# eps.net
KiCad netlist of a schematic drawn in EAGLE
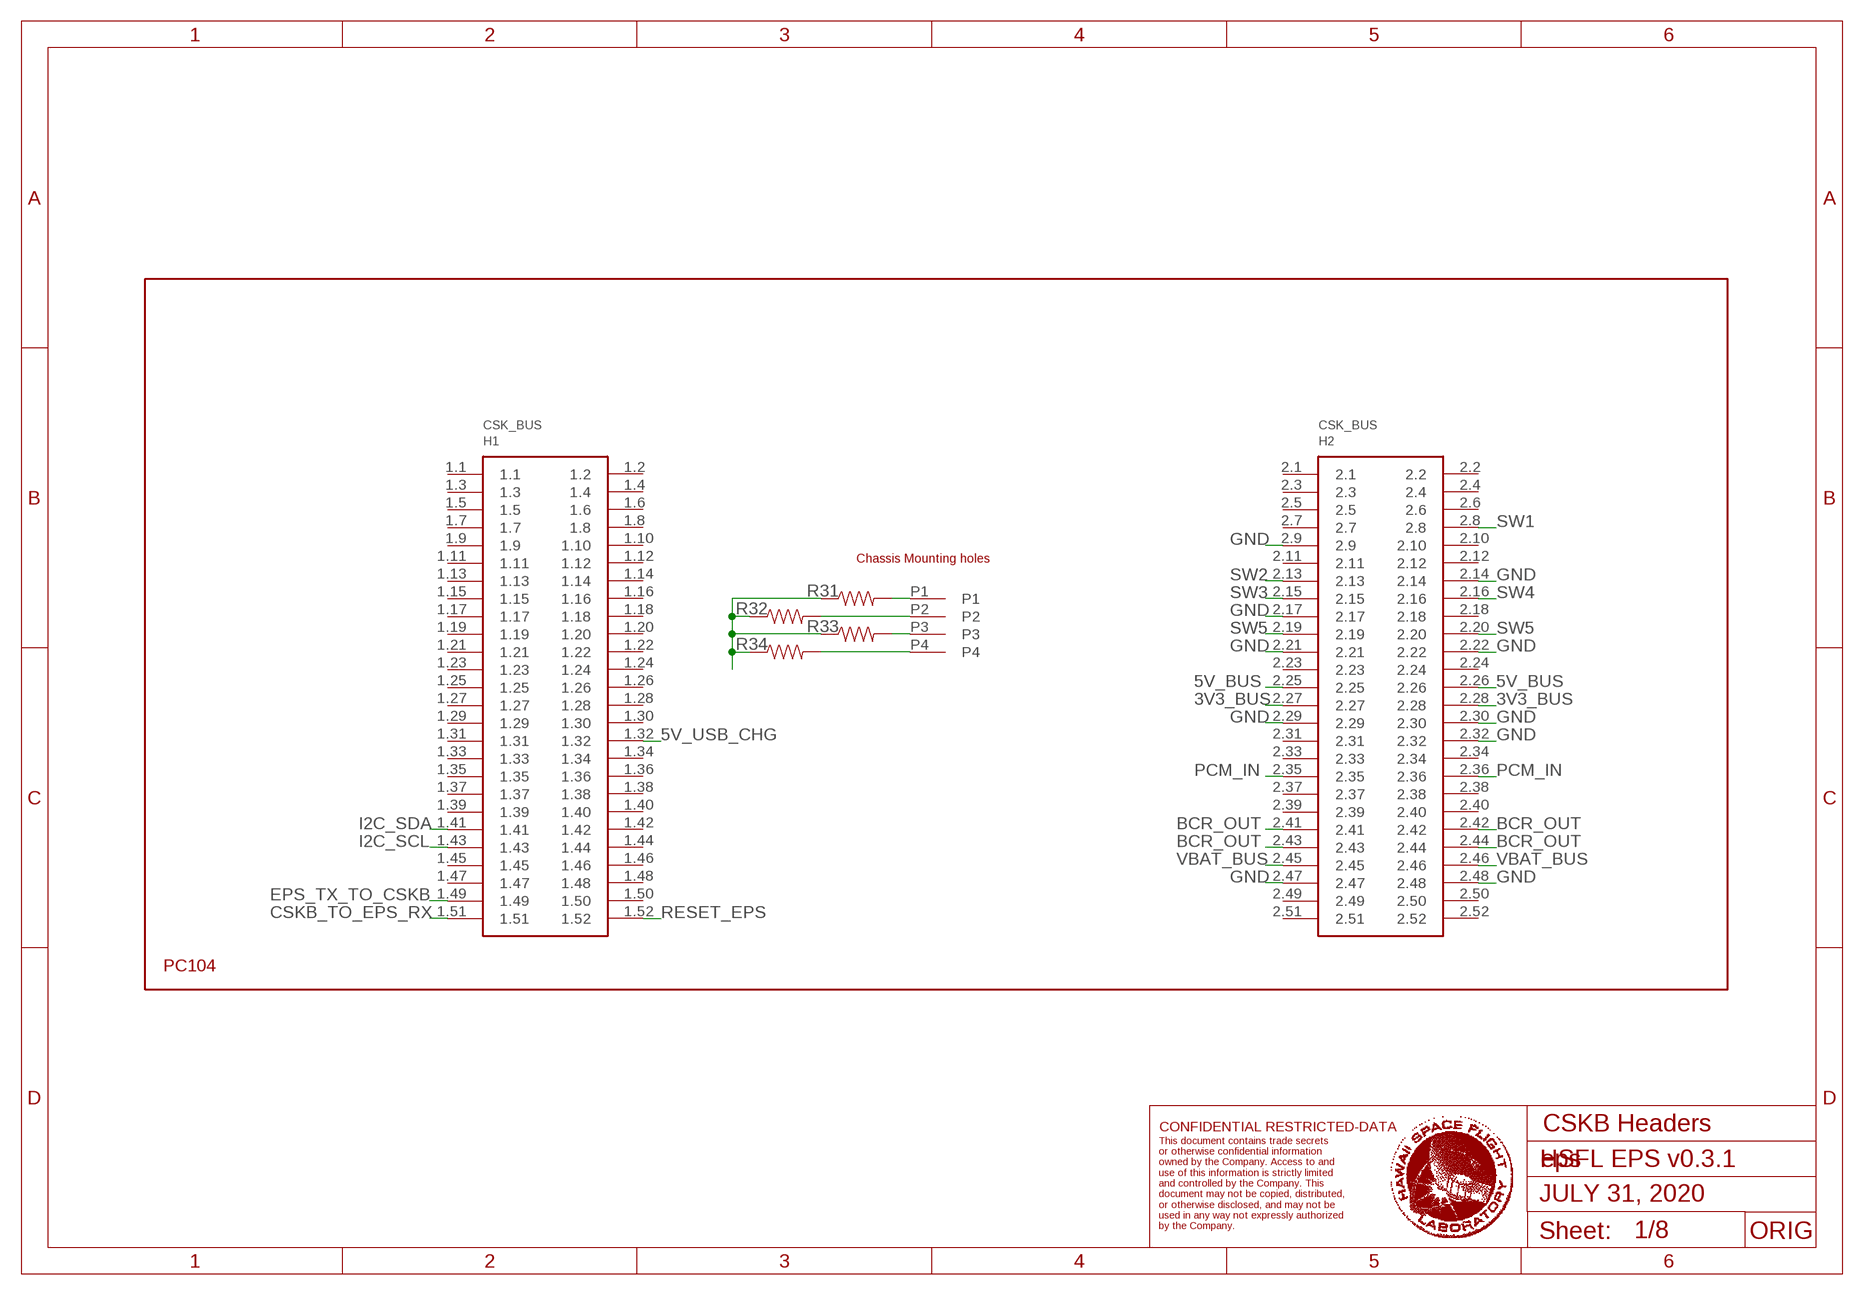
[diagram p0: schematic, sheet 1]
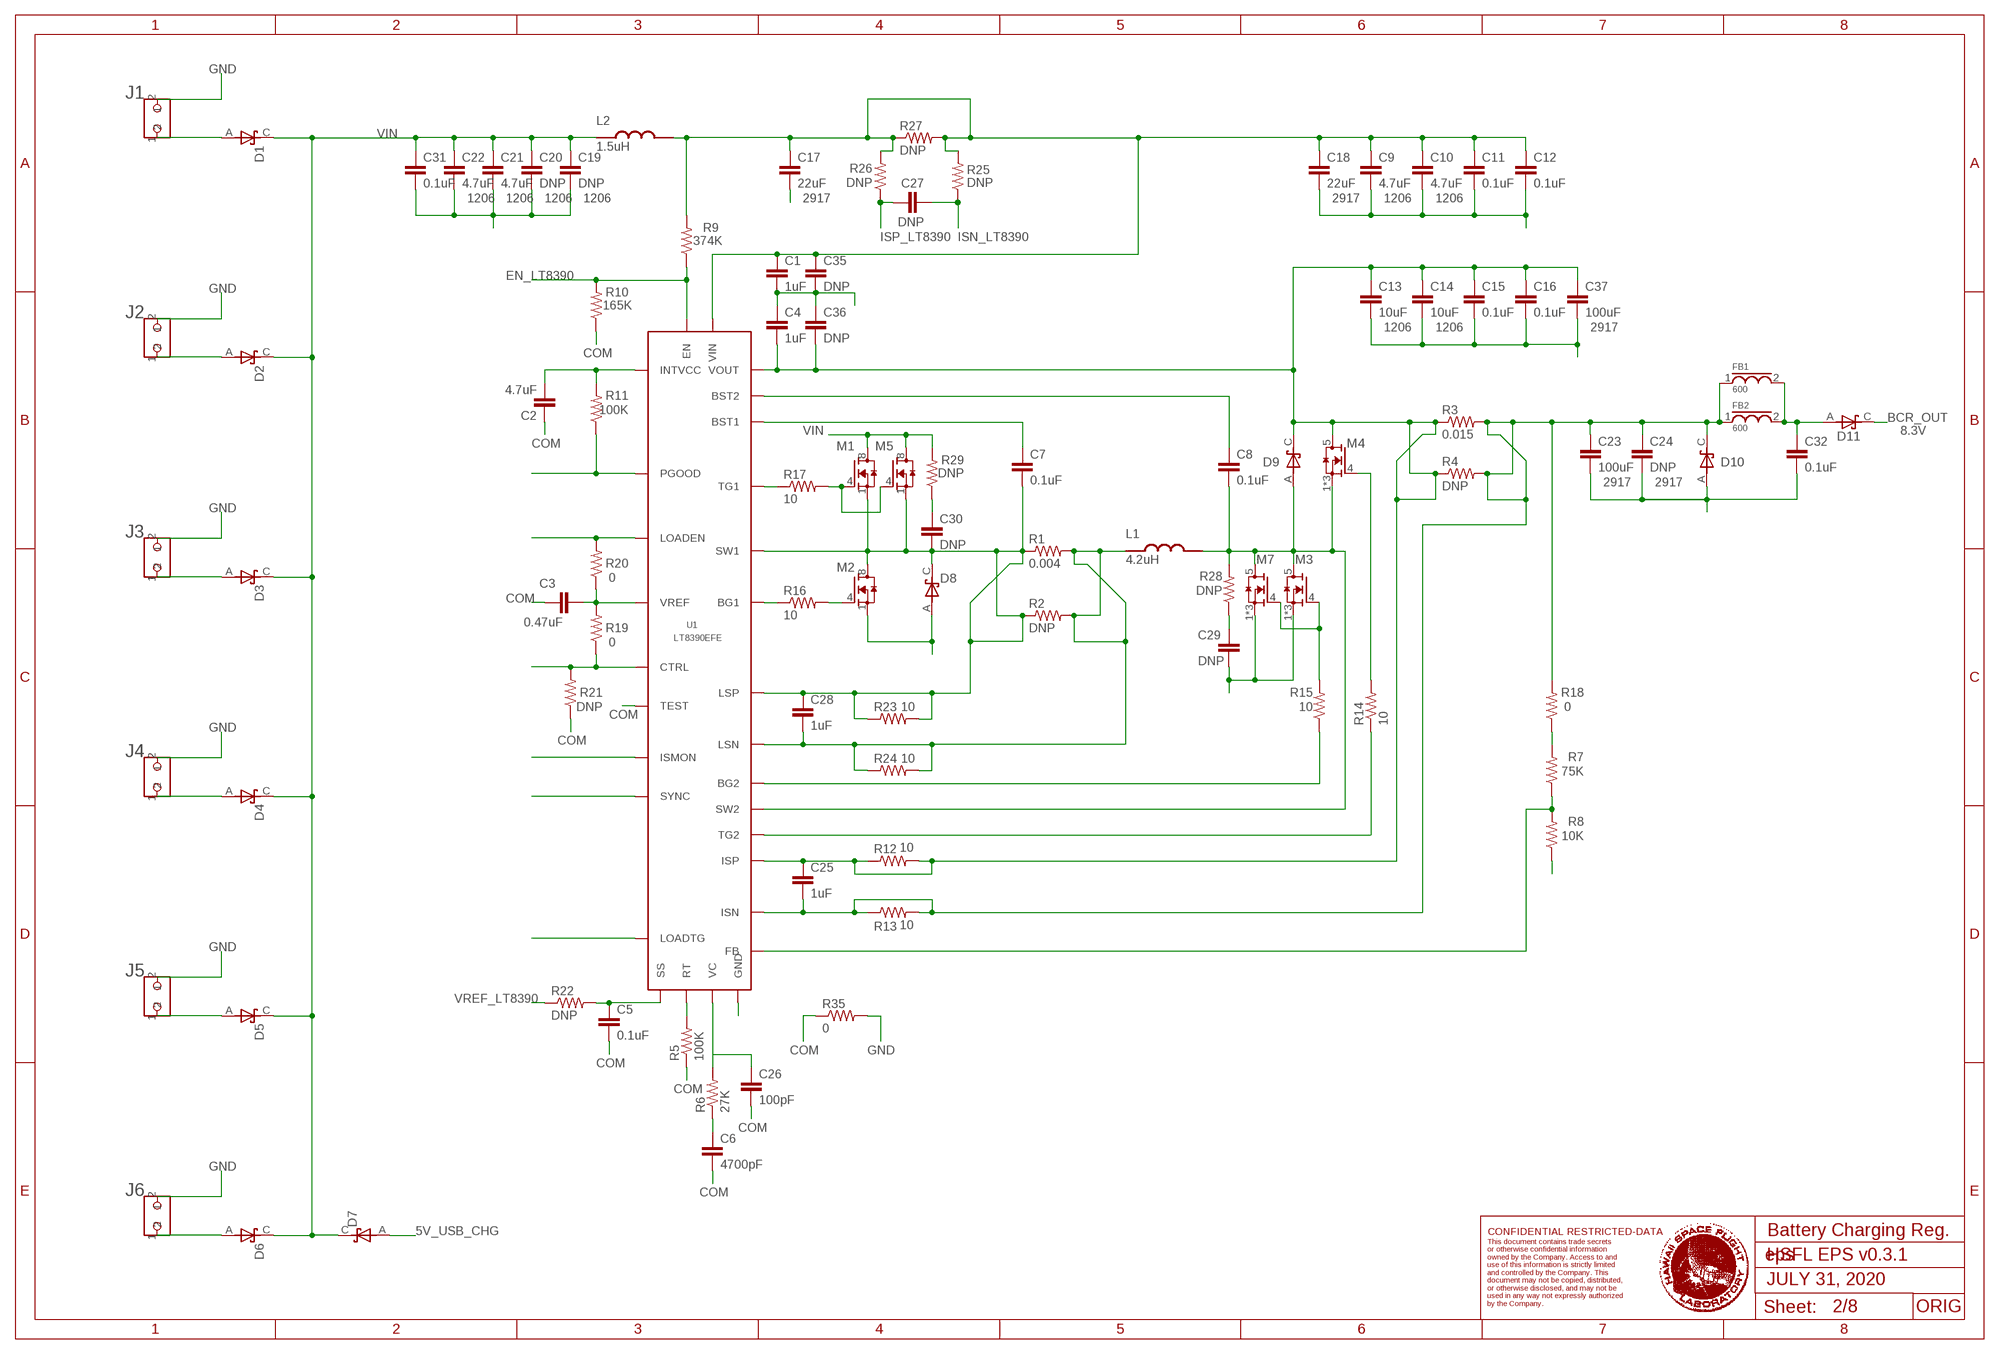
[diagram p1: schematic, sheet 2]
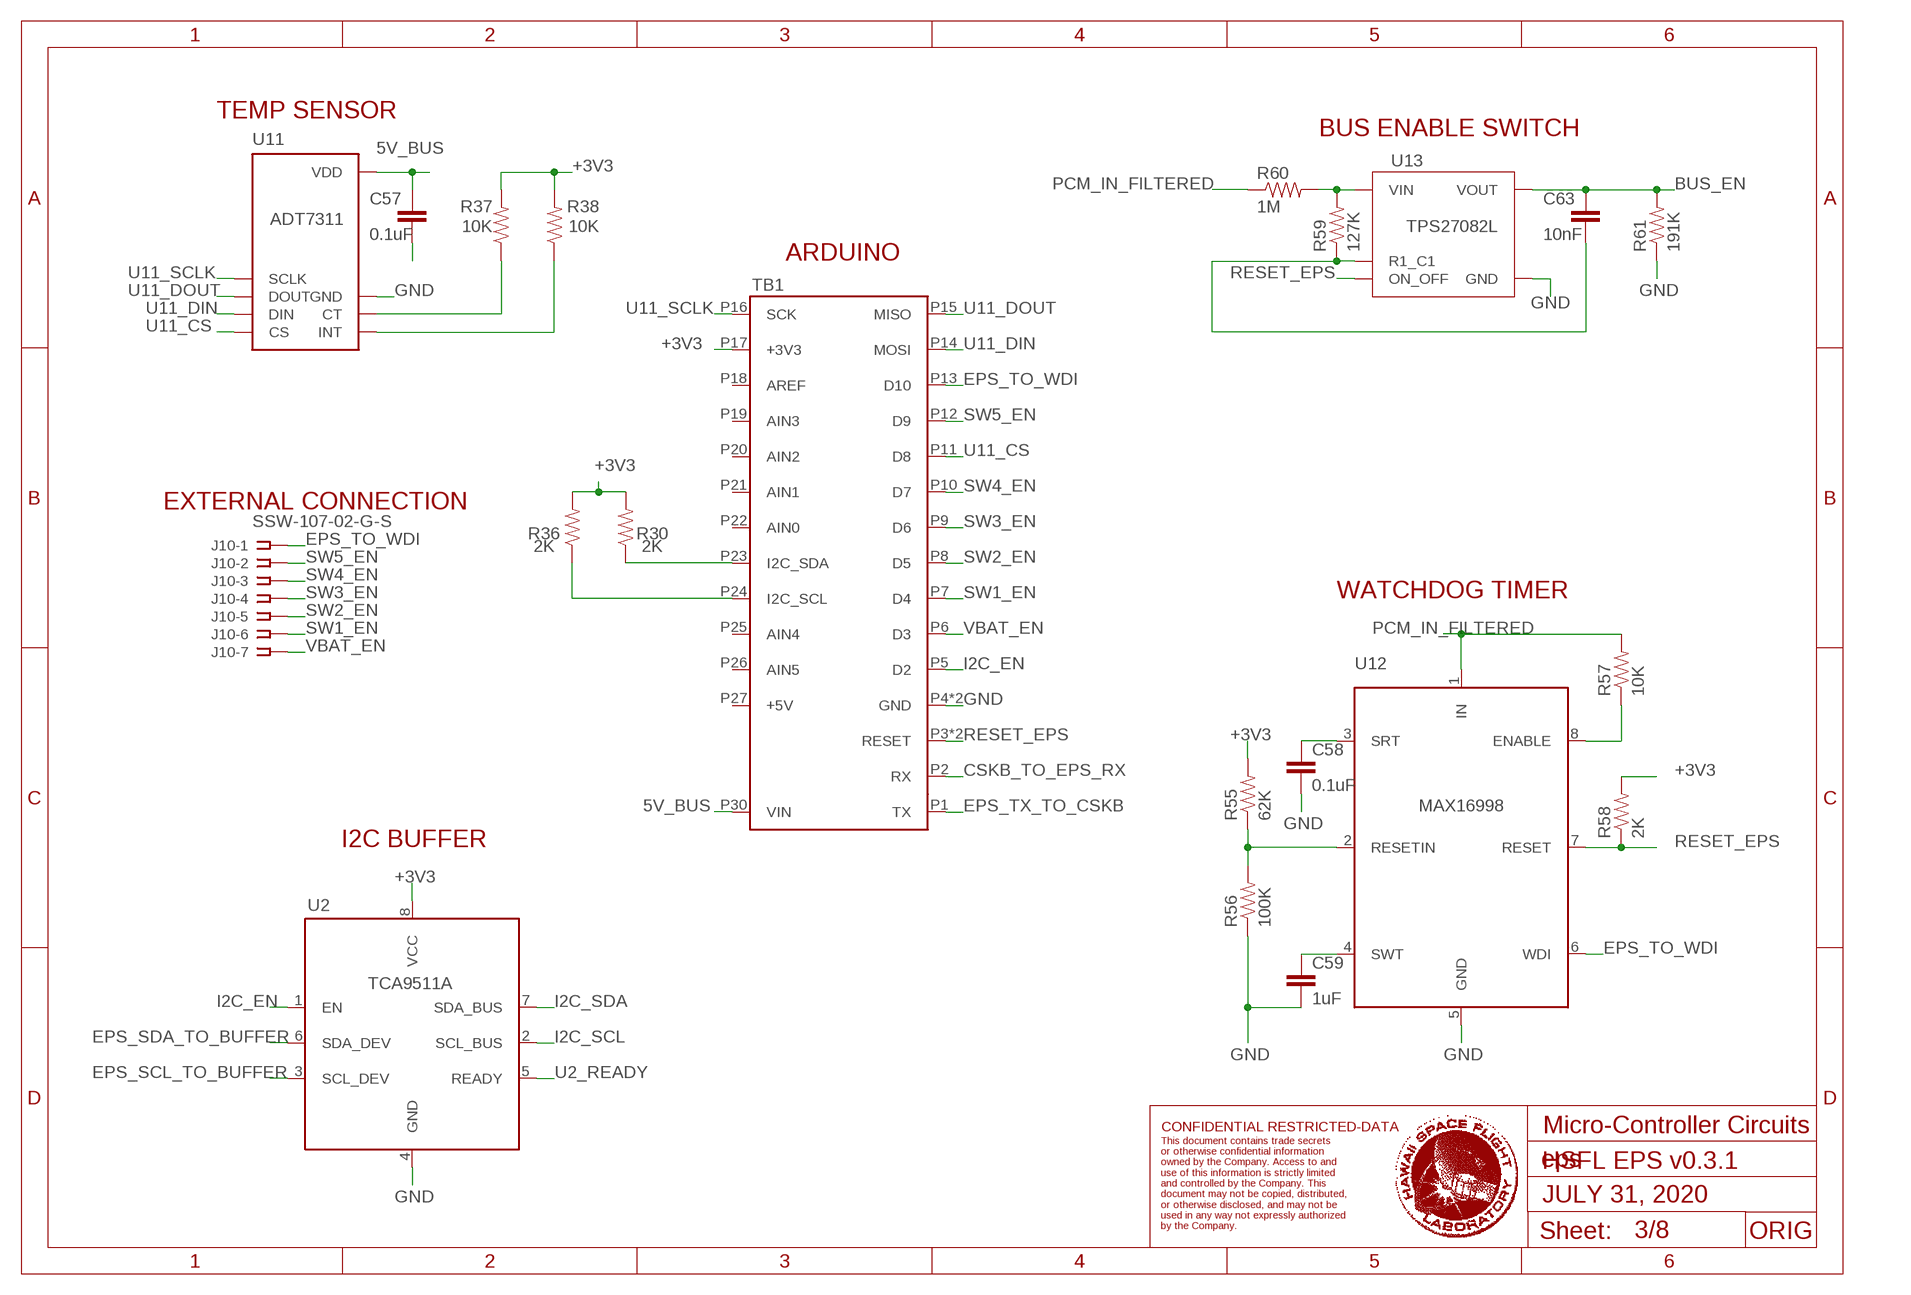
[diagram p2: schematic, sheet 3]
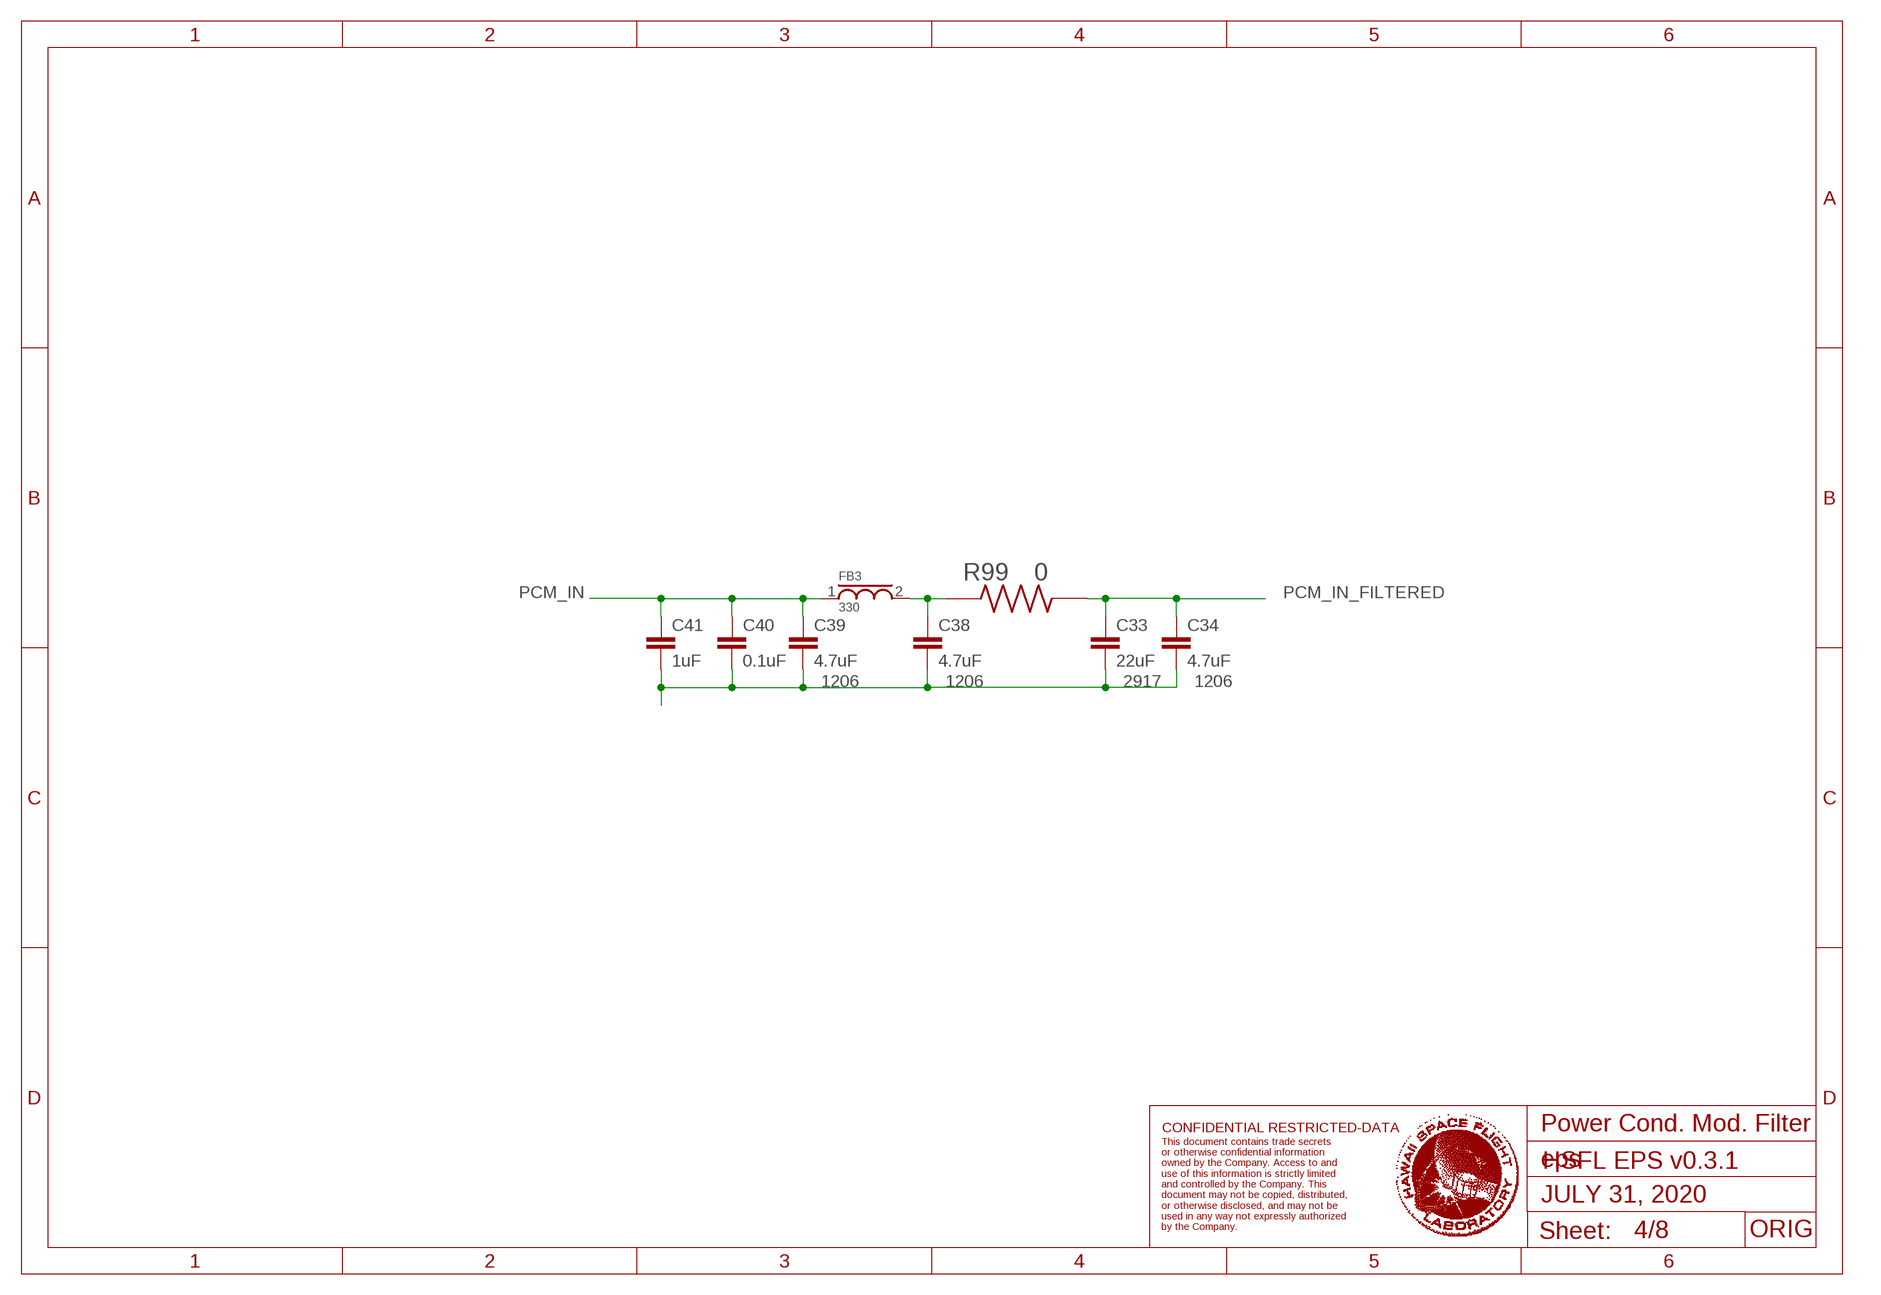
[diagram p3: schematic, sheet 4]
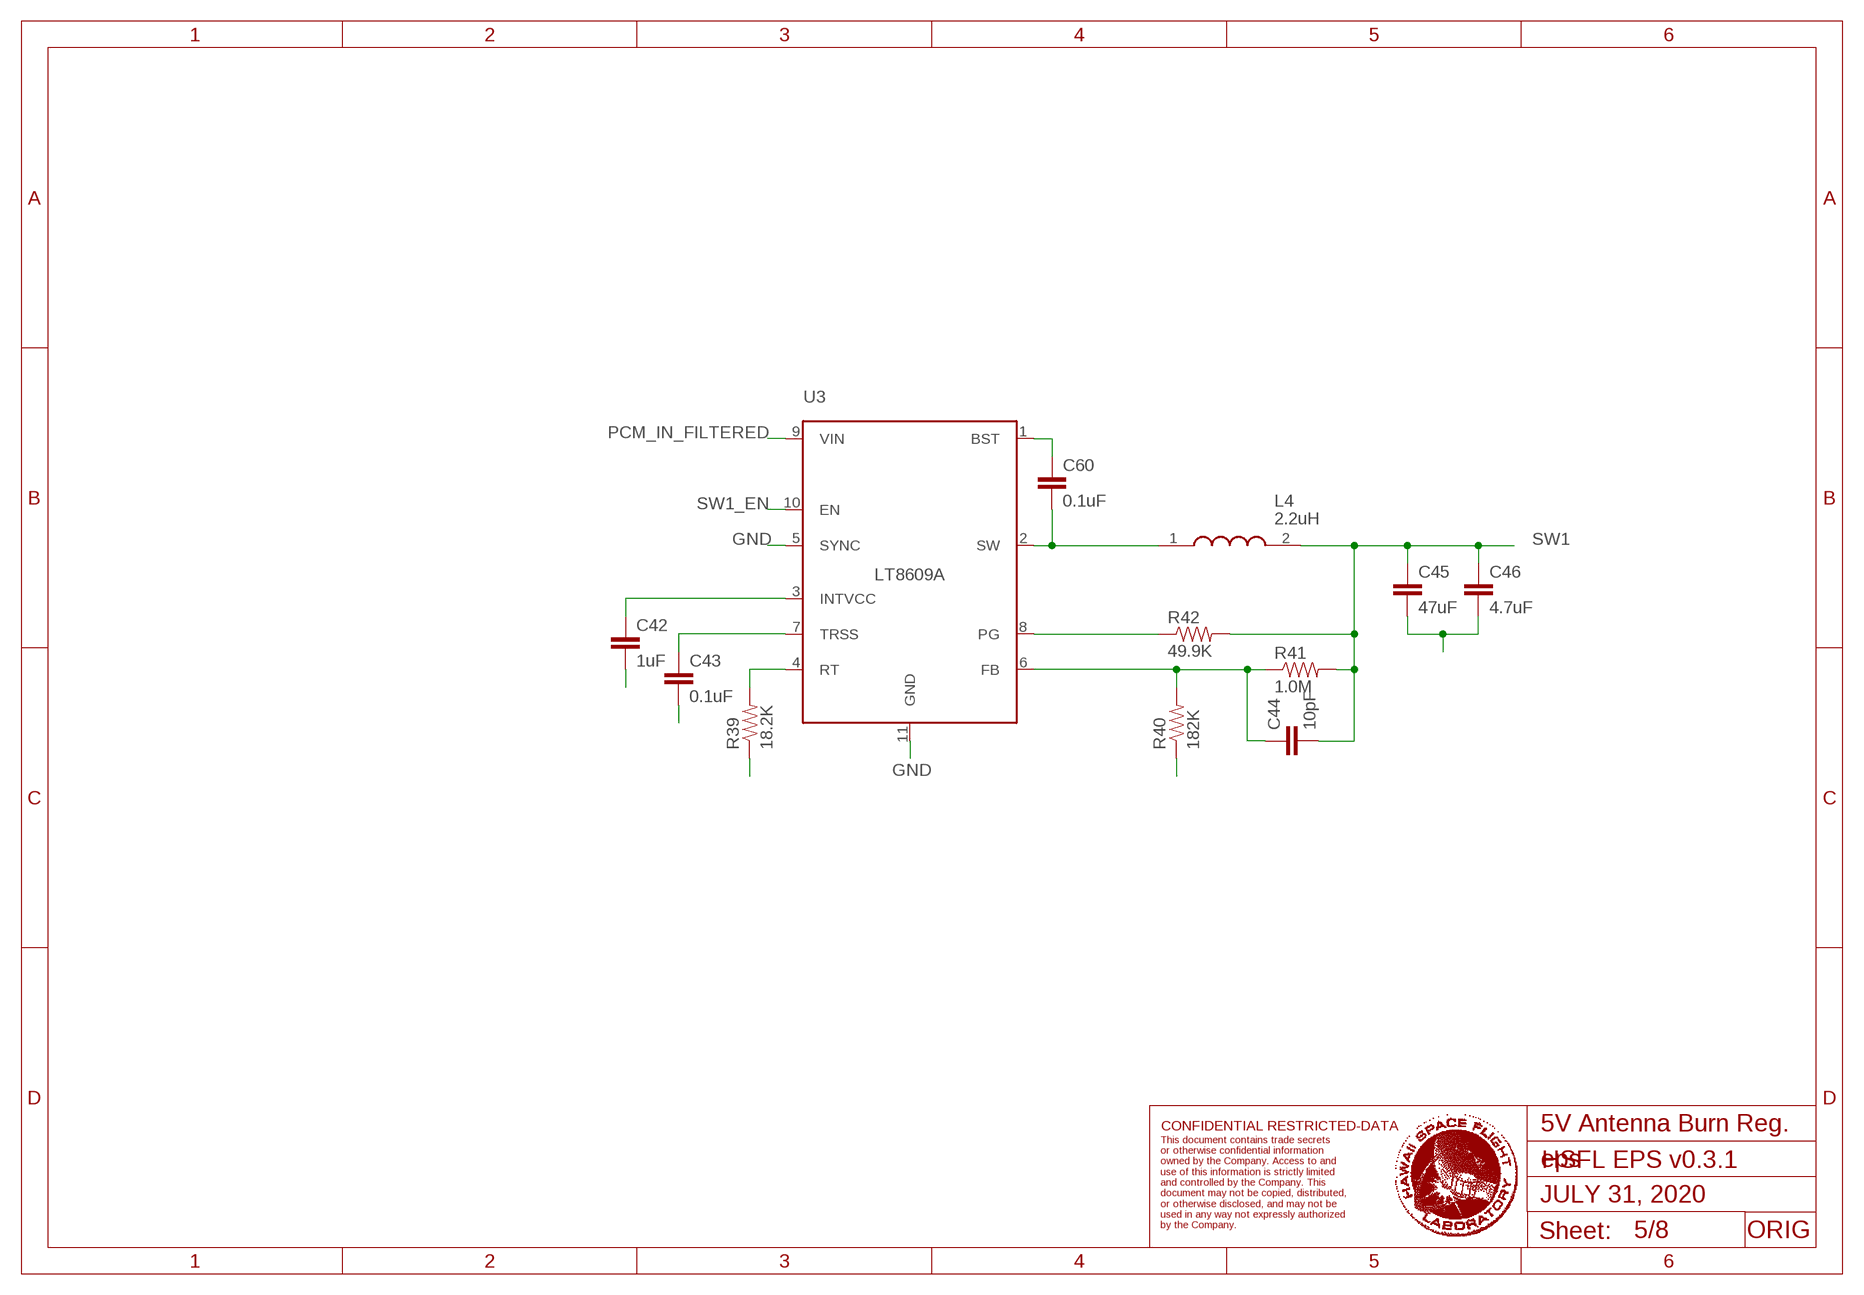
[diagram p4: schematic, sheet 5]
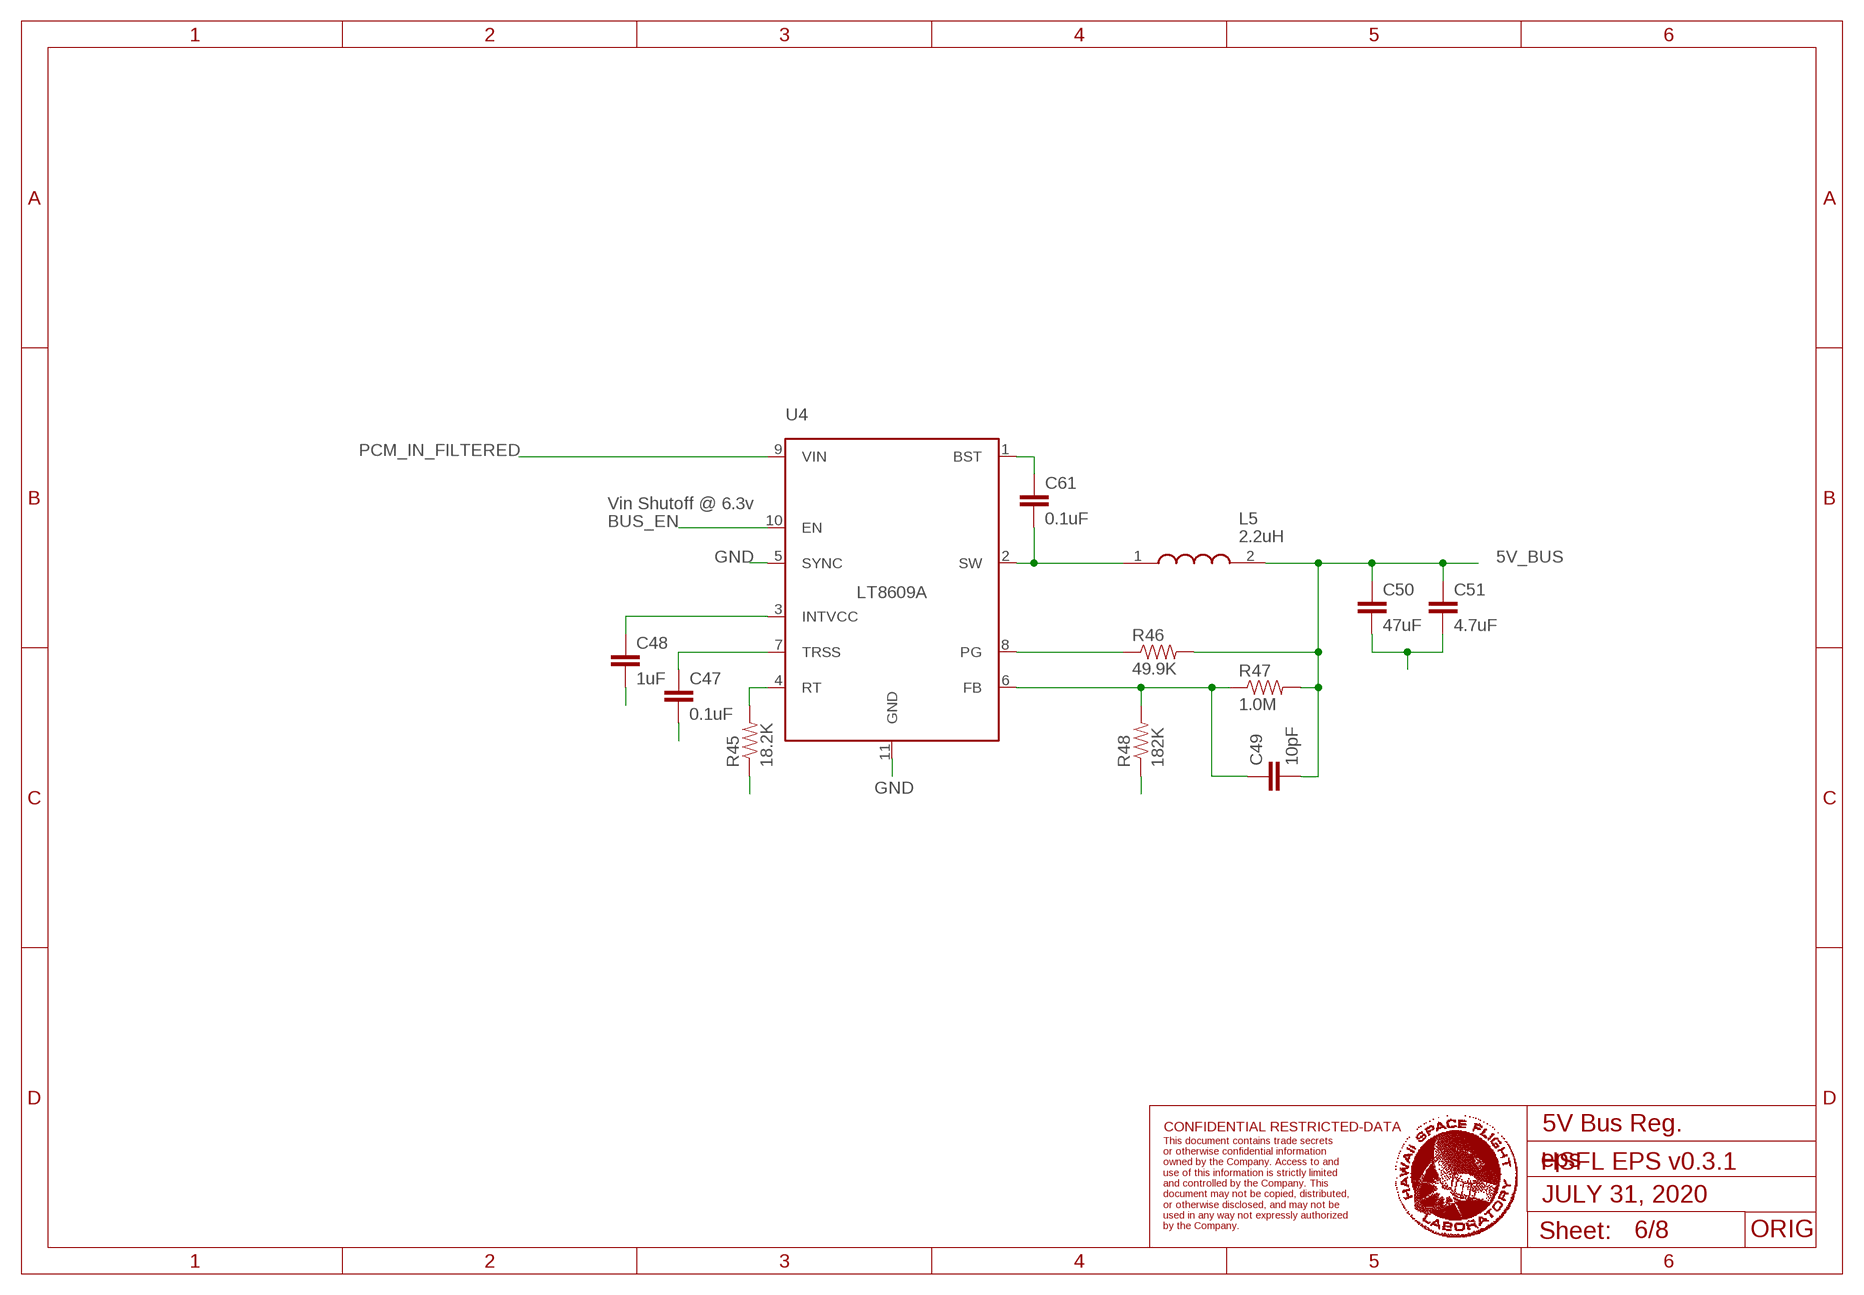
[diagram p5: schematic, sheet 6]
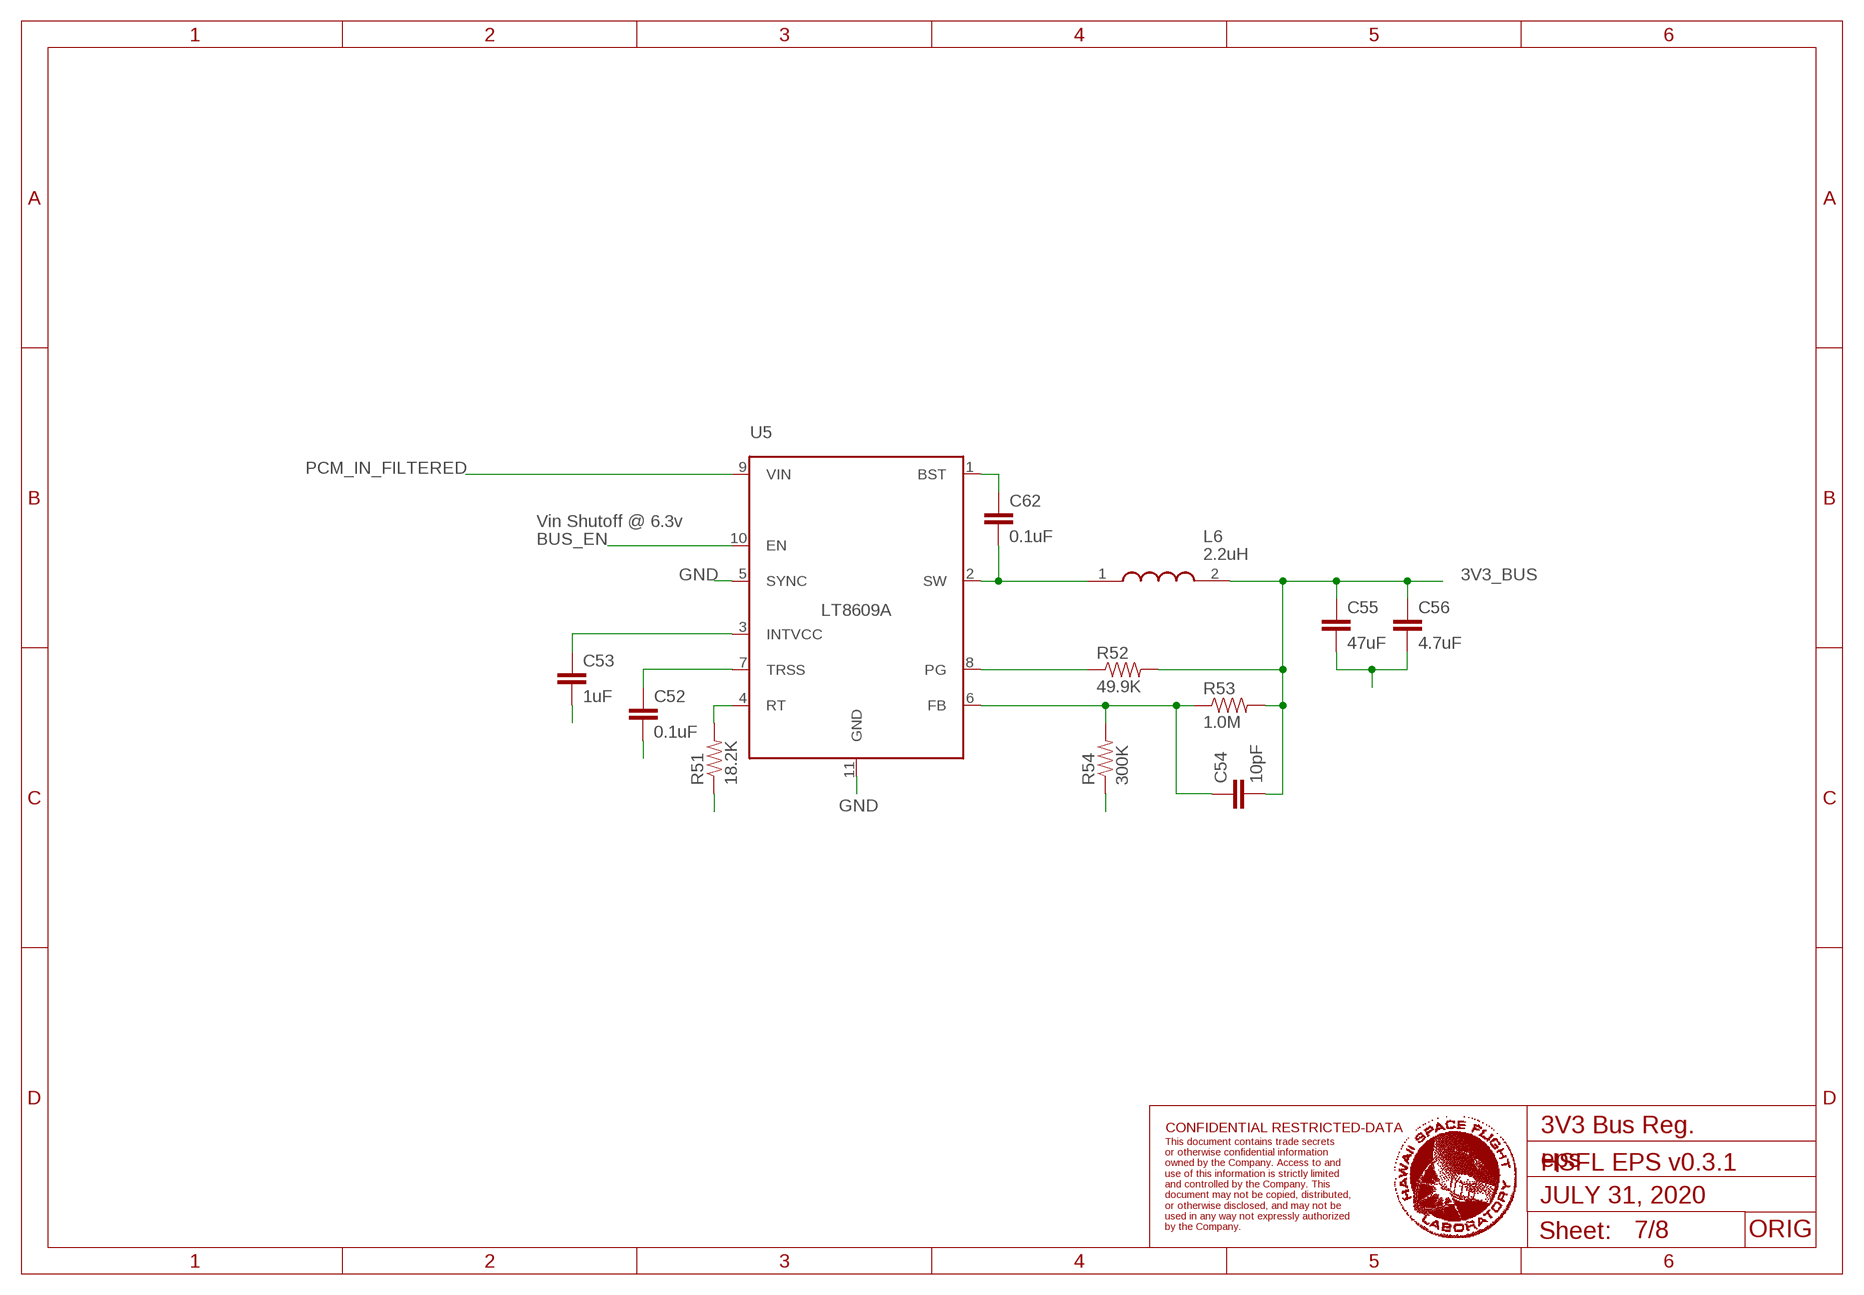
[diagram p6: schematic, sheet 7]
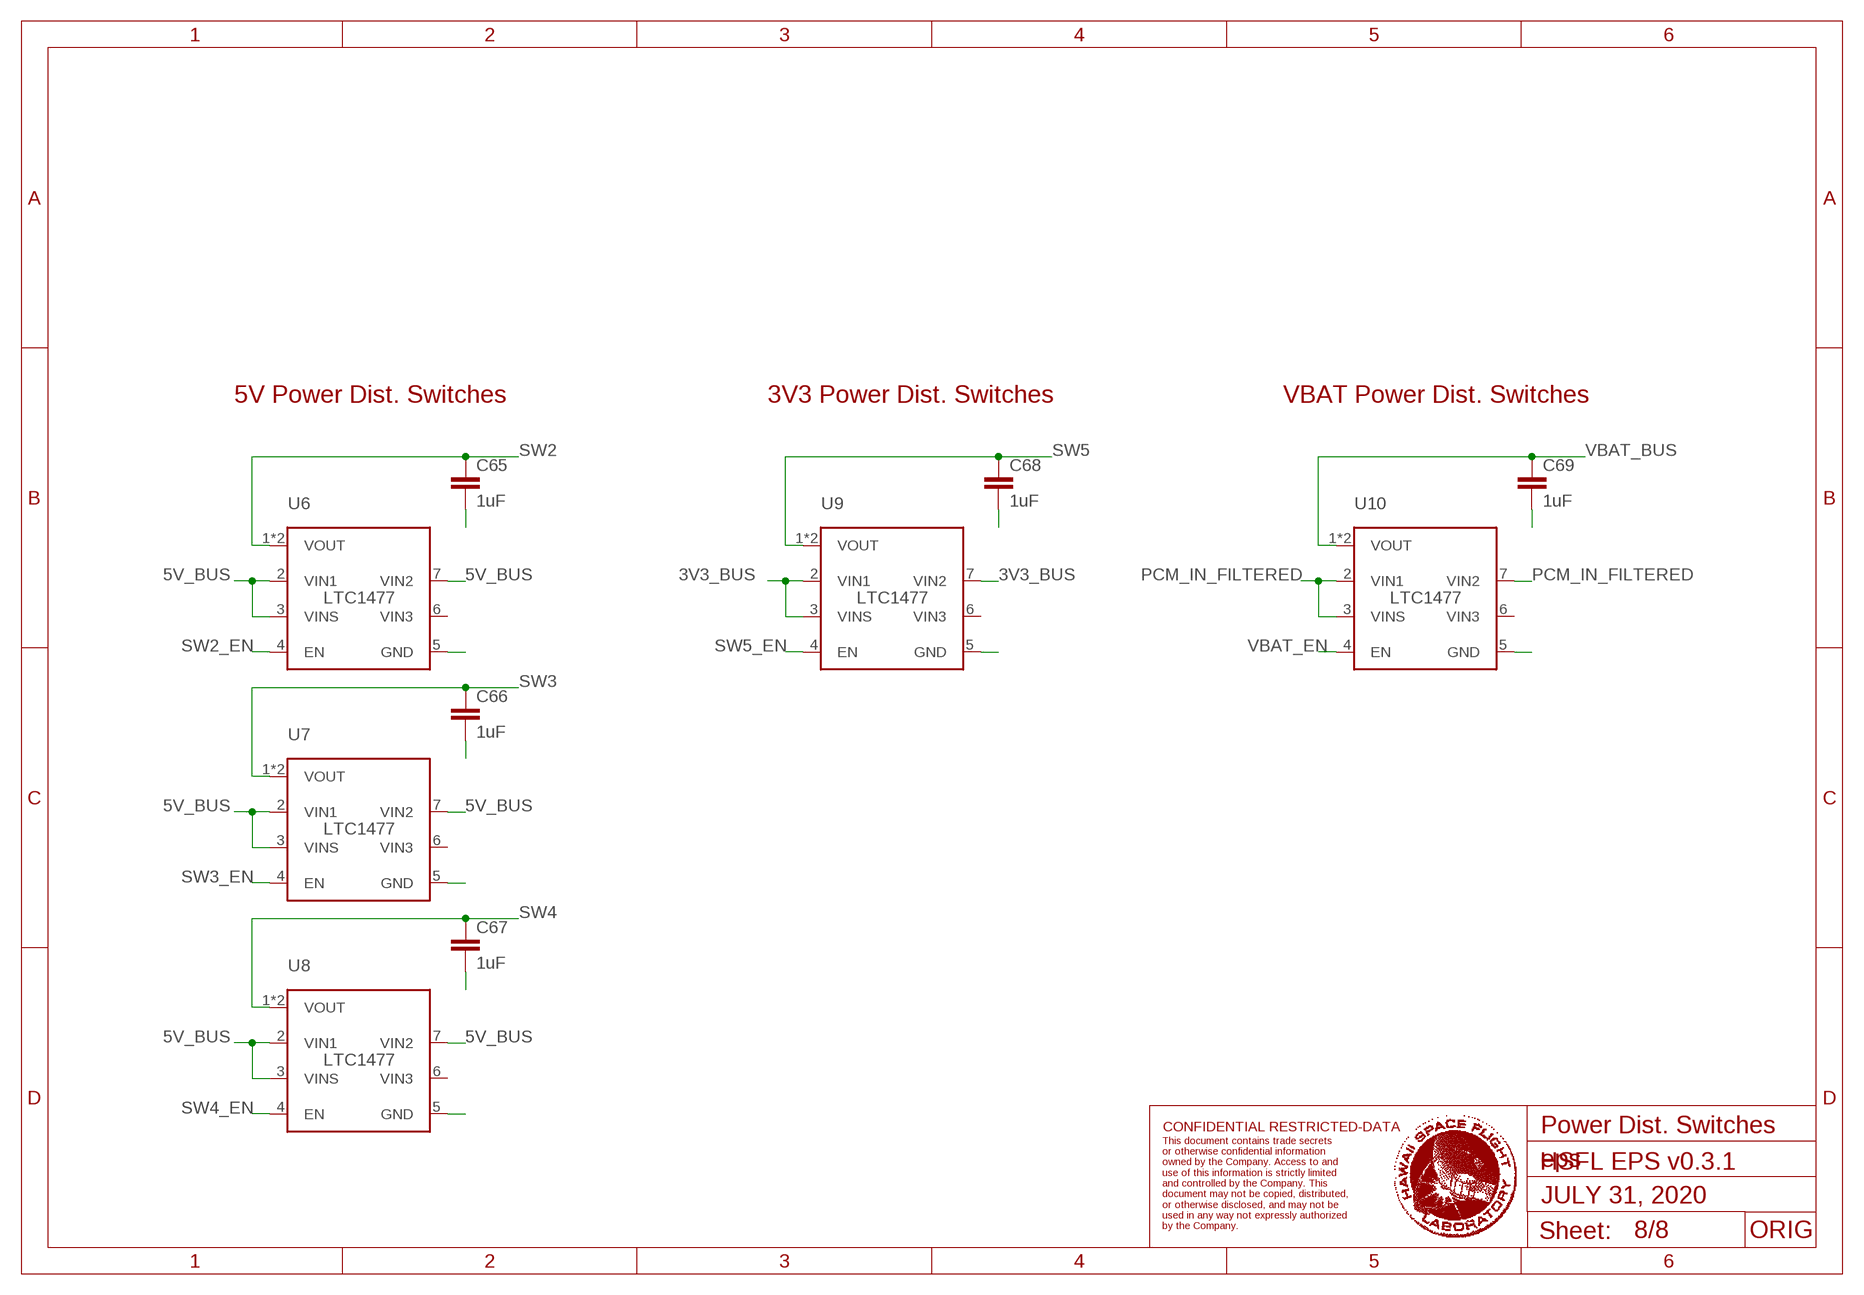
[diagram p7: schematic, sheet 8]

(export (version "E")
  (design (tool "Eeschema 10.0.6"))
  (components
    (comp (ref "C52")
      (value "0.1uF")
      (footprint "eagle-import:0805")
      (libsource (lib "eagle-import") (part "CAP0805"))
    )
    (comp (ref "C53")
      (value "1uF")
      (footprint "eagle-import:0805")
      (libsource (lib "eagle-import") (part "CAP0805"))
    )
    (comp (ref "C54")
      (value "10pF")
      (footprint "eagle-import:0805")
      (libsource (lib "eagle-import") (part "CAP0805"))
    )
    (comp (ref "C55")
      (value "47uF")
      (footprint "eagle-import:1210")
      (libsource (lib "eagle-import") (part "CAP1210"))
    )
    (comp (ref "C56")
      (value "4.7uF")
      (footprint "eagle-import:0805")
      (libsource (lib "eagle-import") (part "CAP0805"))
    )
    (comp (ref "C62")
      (value "0.1uF")
      (footprint "eagle-import:0805")
      (libsource (lib "eagle-import") (part "CAP0805"))
    )
    (comp (ref "L6")
      (value "2.2uH")
      (footprint "eagle-import:XFL4030472MEB")
      (fields
        (field (name "ARROW_PART_NUMBER") "XFL4020-222MEC")
        (field (name "MOUSER_PART_NUMBER") "994-XFL4020-222MEC")
      )
      (libsource (lib "eagle-import") (part "XFL4020-222MEC"))
    )
    (comp (ref "R51")
      (value "18.2K")
      (footprint "eagle-import:0805")
      (libsource (lib "eagle-import") (part "RESISTOR0805-RES"))
    )
    (comp (ref "R52")
      (value "49.9K")
      (footprint "eagle-import:0805")
      (libsource (lib "eagle-import") (part "RESISTOR0805-RES"))
    )
    (comp (ref "R53")
      (value "1.0M")
      (footprint "eagle-import:0805")
      (libsource (lib "eagle-import") (part "RESISTOR0805-RES"))
    )
    (comp (ref "R54")
      (value "300K")
      (footprint "eagle-import:0805")
      (libsource (lib "eagle-import") (part "RESISTOR0805-RES"))
    )
    (comp (ref "U5")
      (value "LT8609A")
      (footprint "eagle-import:MSOP-10_MSE")
      (libsource (lib "eagle-import") (part "LT8609A"))
    )
    (comp (ref "C42")
      (value "1uF")
      (footprint "eagle-import:0805")
      (libsource (lib "eagle-import") (part "CAP0805"))
    )
    (comp (ref "C43")
      (value "0.1uF")
      (footprint "eagle-import:0805")
      (libsource (lib "eagle-import") (part "CAP0805"))
    )
    (comp (ref "C44")
      (value "10pF")
      (footprint "eagle-import:0805")
      (libsource (lib "eagle-import") (part "CAP0805"))
    )
    (comp (ref "C45")
      (value "47uF")
      (footprint "eagle-import:1210")
      (libsource (lib "eagle-import") (part "CAP1210"))
    )
    (comp (ref "C46")
      (value "4.7uF")
      (footprint "eagle-import:0805")
      (libsource (lib "eagle-import") (part "CAP0805"))
    )
    (comp (ref "C60")
      (value "0.1uF")
      (footprint "eagle-import:0805")
      (libsource (lib "eagle-import") (part "CAP0805"))
    )
    (comp (ref "L4")
      (value "2.2uH")
      (footprint "eagle-import:XFL4030472MEB")
      (fields
        (field (name "ARROW_PART_NUMBER") "XFL4020-222MEC")
        (field (name "MOUSER_PART_NUMBER") "994-XFL4020-222MEC")
      )
      (libsource (lib "eagle-import") (part "XFL4020-222MEC"))
    )
    (comp (ref "R39")
      (value "18.2K")
      (footprint "eagle-import:0805")
      (libsource (lib "eagle-import") (part "RESISTOR0805-RES"))
    )
    (comp (ref "R40")
      (value "182K")
      (footprint "eagle-import:0805")
      (libsource (lib "eagle-import") (part "RESISTOR0805-RES"))
    )
    (comp (ref "R41")
      (value "1.0M")
      (footprint "eagle-import:0805")
      (libsource (lib "eagle-import") (part "RESISTOR0805-RES"))
    )
    (comp (ref "R42")
      (value "49.9K")
      (footprint "eagle-import:0805")
      (libsource (lib "eagle-import") (part "RESISTOR0805-RES"))
    )
    (comp (ref "U3")
      (value "LT8609A")
      (footprint "eagle-import:MSOP-10_MSE")
      (libsource (lib "eagle-import") (part "LT8609A"))
    )
    (comp (ref "H1")
      (value "PC104_WCONN")
      (footprint "eagle-import:PC104_WCONN")
      (libsource (lib "eagle-import") (part "PC104_WCONN"))
    )
    (comp (ref "R31")
      (value "1M")
      (footprint "eagle-import:0805")
      (libsource (lib "eagle-import") (part "RESISTOR0805-RES"))
    )
    (comp (ref "R32")
      (value "1M")
      (footprint "eagle-import:0805")
      (libsource (lib "eagle-import") (part "RESISTOR0805-RES"))
    )
    (comp (ref "R33")
      (value "1M")
      (footprint "eagle-import:0805")
      (libsource (lib "eagle-import") (part "RESISTOR0805-RES"))
    )
    (comp (ref "R34")
      (value "1M")
      (footprint "eagle-import:0805")
      (libsource (lib "eagle-import") (part "RESISTOR0805-RES"))
    )
    (comp (ref "C57")
      (value "0.1uF")
      (footprint "eagle-import:0805")
      (libsource (lib "eagle-import") (part "CAP0805"))
    )
    (comp (ref "C58")
      (value "0.1uF")
      (footprint "eagle-import:0805")
      (libsource (lib "eagle-import") (part "CAP0805"))
    )
    (comp (ref "C59")
      (value "1uF")
      (footprint "eagle-import:0805")
      (libsource (lib "eagle-import") (part "CAP0805"))
    )
    (comp (ref "C63")
      (value "10nF")
      (footprint "eagle-import:0805")
      (libsource (lib "eagle-import") (part "CAP0805"))
    )
    (comp (ref "J10")
      (value "SSW-107-02-G-S")
      (footprint "eagle-import:SSW-107-02-G-S")
      (fields (field (name "MF") "Samtec Inc."))
      (libsource (lib "eagle-import") (part "SSW-107-02-G-S"))
    )
    (comp (ref "R30")
      (value "2K")
      (footprint "eagle-import:0805")
      (libsource (lib "eagle-import") (part "RESISTOR0805-RES"))
    )
    (comp (ref "R36")
      (value "2K")
      (footprint "eagle-import:0805")
      (libsource (lib "eagle-import") (part "RESISTOR0805-RES"))
    )
    (comp (ref "R37")
      (value "10K")
      (footprint "eagle-import:0805")
      (libsource (lib "eagle-import") (part "RESISTOR0805-RES"))
    )
    (comp (ref "R38")
      (value "10K")
      (footprint "eagle-import:0805")
      (libsource (lib "eagle-import") (part "RESISTOR0805-RES"))
    )
    (comp (ref "R55")
      (value "62K")
      (footprint "eagle-import:0805")
      (libsource (lib "eagle-import") (part "RESISTOR0805-RES"))
    )
    (comp (ref "R56")
      (value "100K")
      (footprint "eagle-import:0805")
      (libsource (lib "eagle-import") (part "RESISTOR0805-RES"))
    )
    (comp (ref "R57")
      (value "10K")
      (footprint "eagle-import:0805")
      (libsource (lib "eagle-import") (part "RESISTOR0805-RES"))
    )
    (comp (ref "R58")
      (value "2K")
      (footprint "eagle-import:0805")
      (libsource (lib "eagle-import") (part "RESISTOR0805-RES"))
    )
    (comp (ref "R59")
      (value "127K")
      (footprint "eagle-import:0805")
      (libsource (lib "eagle-import") (part "RESISTOR0805-RES"))
    )
    (comp (ref "R60")
      (value "1M")
      (footprint "eagle-import:0805")
      (libsource (lib "eagle-import") (part "RESISTOR0805-RES"))
    )
    (comp (ref "R61")
      (value "191K")
      (footprint "eagle-import:0805")
      (libsource (lib "eagle-import") (part "RESISTOR0805-RES"))
    )
    (comp (ref "TB1")
      (value "ARDUINO_NANO")
      (footprint "eagle-import:SHIELD_ARDUINO_NANO")
      (fields (field (name "MF") "Arduino") (field (name "MP") "ARDUINO NANO"))
      (libsource (lib "eagle-import") (part "ARDUINO_NANO"))
    )
    (comp (ref "U2")
      (value "TCA9511A")
      (footprint "eagle-import:SOP65P490X110-8N")
      (libsource (lib "eagle-import") (part "TCA9511A"))
    )
    (comp (ref "U11")
      (value "ADT7311")
      (footprint "eagle-import:SOIC-8")
      (libsource (lib "eagle-import") (part "ADT7311"))
    )
    (comp (ref "U12")
      (value "MAX16998AAUA+")
      (footprint "eagle-import:21-0036K_MXM")
      (libsource (lib "eagle-import") (part "MAX16998AAUA+"))
    )
    (comp (ref "U13")
      (value "Value")
      (footprint "eagle-import:DDC0006A_N")
      (fields (field (name "MANUFACTURER") "Texas Instruments") (field (name "PARTNUMBER") "TPS27082LDDC"))
      (libsource (lib "eagle-import") (part "TPS27082LDDCR"))
    )
    (comp (ref "C1")
      (value "1uF")
      (footprint "eagle-import:0805")
      (libsource (lib "eagle-import") (part "CAP0805"))
    )
    (comp (ref "C2")
      (value "4.7uF")
      (footprint "eagle-import:0805")
      (libsource (lib "eagle-import") (part "CAP0805"))
    )
    (comp (ref "C3")
      (value "0.47uF")
      (footprint "eagle-import:0805")
      (libsource (lib "eagle-import") (part "CAP0805"))
    )
    (comp (ref "C4")
      (value "1uF")
      (footprint "eagle-import:0805")
      (libsource (lib "eagle-import") (part "CAP0805"))
    )
    (comp (ref "C5")
      (value "0.1uF")
      (footprint "eagle-import:0805")
      (libsource (lib "eagle-import") (part "CAP0805"))
    )
    (comp (ref "C6")
      (value "4700pF")
      (footprint "eagle-import:0805")
      (libsource (lib "eagle-import") (part "CAP0805"))
    )
    (comp (ref "C7")
      (value "0.1uF")
      (footprint "eagle-import:0805")
      (libsource (lib "eagle-import") (part "CAP0805"))
    )
    (comp (ref "C8")
      (value "0.1uF")
      (footprint "eagle-import:0805")
      (libsource (lib "eagle-import") (part "CAP0805"))
    )
    (comp (ref "C9")
      (value "4.7uF")
      (footprint "eagle-import:1206")
      (libsource (lib "eagle-import") (part "CAP1206"))
    )
    (comp (ref "C10")
      (value "4.7uF")
      (footprint "eagle-import:1206")
      (libsource (lib "eagle-import") (part "CAP1206"))
    )
    (comp (ref "C11")
      (value "0.1uF")
      (footprint "eagle-import:0805")
      (libsource (lib "eagle-import") (part "CAP0805"))
    )
    (comp (ref "C12")
      (value "0.1uF")
      (footprint "eagle-import:0805")
      (libsource (lib "eagle-import") (part "CAP0805"))
    )
    (comp (ref "C13")
      (value "10uF")
      (footprint "eagle-import:1206")
      (libsource (lib "eagle-import") (part "CAP1206"))
    )
    (comp (ref "C14")
      (value "10uF")
      (footprint "eagle-import:1206")
      (libsource (lib "eagle-import") (part "CAP1206"))
    )
    (comp (ref "C15")
      (value "0.1uF")
      (footprint "eagle-import:1210")
      (libsource (lib "eagle-import") (part "CAP1210"))
    )
    (comp (ref "C16")
      (value "0.1uF")
      (footprint "eagle-import:1210")
      (libsource (lib "eagle-import") (part "CAP1210"))
    )
    (comp (ref "C17")
      (value "22uF")
      (footprint "eagle-import:CAPMP7343X430N")
      (libsource (lib "eagle-import") (part "CAP_29172917"))
    )
    (comp (ref "C18")
      (value "22uF")
      (footprint "eagle-import:CAPMP7343X430N")
      (libsource (lib "eagle-import") (part "CAP_29172917"))
    )
    (comp (ref "C19")
      (value "DNP")
      (footprint "eagle-import:1206")
      (libsource (lib "eagle-import") (part "CAP1206"))
    )
    (comp (ref "C20")
      (value "DNP")
      (footprint "eagle-import:1206")
      (libsource (lib "eagle-import") (part "CAP1206"))
    )
    (comp (ref "C21")
      (value "4.7uF")
      (footprint "eagle-import:1206")
      (libsource (lib "eagle-import") (part "CAP1206"))
    )
    (comp (ref "C22")
      (value "4.7uF")
      (footprint "eagle-import:1206")
      (libsource (lib "eagle-import") (part "CAP1206"))
    )
    (comp (ref "C23")
      (value "100uF")
      (footprint "eagle-import:CAPMP7343X430N")
      (libsource (lib "eagle-import") (part "CAP_29172917"))
    )
    (comp (ref "C24")
      (value "DNP")
      (footprint "eagle-import:CAPMP7343X430N")
      (libsource (lib "eagle-import") (part "CAP_29172917"))
    )
    (comp (ref "C25")
      (value "1uF")
      (footprint "eagle-import:0805")
      (libsource (lib "eagle-import") (part "CAP0805"))
    )
    (comp (ref "C26")
      (value "100pF")
      (footprint "eagle-import:0805")
      (libsource (lib "eagle-import") (part "CAP0805"))
    )
    (comp (ref "C27")
      (value "DNP")
      (footprint "eagle-import:0805")
      (libsource (lib "eagle-import") (part "CAP0805"))
    )
    (comp (ref "C28")
      (value "1uF")
      (footprint "eagle-import:0805")
      (libsource (lib "eagle-import") (part "CAP0805"))
    )
    (comp (ref "C29")
      (value "DNP")
      (footprint "eagle-import:0805")
      (libsource (lib "eagle-import") (part "CAP0805"))
    )
    (comp (ref "C30")
      (value "DNP")
      (footprint "eagle-import:0805")
      (libsource (lib "eagle-import") (part "CAP0805"))
    )
    (comp (ref "C31")
      (value "0.1uF")
      (footprint "eagle-import:0805")
      (libsource (lib "eagle-import") (part "CAP0805"))
    )
    (comp (ref "C32")
      (value "0.1uF")
      (footprint "eagle-import:0805")
      (libsource (lib "eagle-import") (part "CAP0805"))
    )
    (comp (ref "C35")
      (value "DNP")
      (footprint "eagle-import:1210")
      (libsource (lib "eagle-import") (part "CAP1210"))
    )
    (comp (ref "C36")
      (value "DNP")
      (footprint "eagle-import:1210")
      (libsource (lib "eagle-import") (part "CAP1210"))
    )
    (comp (ref "C37")
      (value "100uF")
      (footprint "eagle-import:CAPMP7343X430N")
      (libsource (lib "eagle-import") (part "CAP_29172917"))
    )
    (comp (ref "D1")
      (value "DNP")
      (footprint "eagle-import:SODFL3616X98N")
      (fields (field (name "MF") "ON Semiconductor") (field (name "MP") "MBR2H100SFT3G"))
      (libsource (lib "eagle-import") (part "MBR2H100SFT3G"))
    )
    (comp (ref "D2")
      (value "DNP")
      (footprint "eagle-import:SODFL3616X98N")
      (fields (field (name "MF") "ON Semiconductor") (field (name "MP") "MBR2H100SFT3G"))
      (libsource (lib "eagle-import") (part "MBR2H100SFT3G"))
    )
    (comp (ref "D3")
      (value "DNP")
      (footprint "eagle-import:SODFL3616X98N")
      (fields (field (name "MF") "ON Semiconductor") (field (name "MP") "MBR2H100SFT3G"))
      (libsource (lib "eagle-import") (part "MBR2H100SFT3G"))
    )
    (comp (ref "D4")
      (value "DNP")
      (footprint "eagle-import:SODFL3616X98N")
      (fields (field (name "MF") "ON Semiconductor") (field (name "MP") "MBR2H100SFT3G"))
      (libsource (lib "eagle-import") (part "MBR2H100SFT3G"))
    )
    (comp (ref "D5")
      (value "DNP")
      (footprint "eagle-import:SODFL3616X98N")
      (fields (field (name "MF") "ON Semiconductor") (field (name "MP") "MBR2H100SFT3G"))
      (libsource (lib "eagle-import") (part "MBR2H100SFT3G"))
    )
    (comp (ref "D6")
      (value "DNP")
      (footprint "eagle-import:SODFL3616X98N")
      (fields (field (name "MF") "ON Semiconductor") (field (name "MP") "MBR2H100SFT3G"))
      (libsource (lib "eagle-import") (part "MBR2H100SFT3G"))
    )
    (comp (ref "D7")
      (value "DNP")
      (footprint "eagle-import:SODFL3616X98N")
      (fields (field (name "MF") "ON Semiconductor") (field (name "MP") "MBR2H100SFT3G"))
      (libsource (lib "eagle-import") (part "MBR2H100SFT3G"))
    )
    (comp (ref "D8")
      (value "DNP")
      (footprint "eagle-import:SODFL3616X98N")
      (fields (field (name "MF") "ON Semiconductor") (field (name "MP") "MBR2H100SFT3G"))
      (libsource (lib "eagle-import") (part "MBR2H100SFT3G"))
    )
    (comp (ref "D9")
      (value "DNP")
      (footprint "eagle-import:SODFL3616X98N")
      (fields (field (name "MF") "ON Semiconductor") (field (name "MP") "MBR2H100SFT3G"))
      (libsource (lib "eagle-import") (part "MBR2H100SFT3G"))
    )
    (comp (ref "D10")
      (value "DNP")
      (footprint "eagle-import:SODFL3616X98N")
      (fields (field (name "MF") "ON Semiconductor") (field (name "MP") "MBR2H100SFT3G"))
      (libsource (lib "eagle-import") (part "MBR2H100SFT3G"))
    )
    (comp (ref "D11")
      (value "DNP")
      (footprint "eagle-import:SODFL3616X98N")
      (fields (field (name "MF") "ON Semiconductor") (field (name "MP") "MBR2H100SFT3G"))
      (libsource (lib "eagle-import") (part "MBR2H100SFT3G"))
    )
    (comp (ref "FB1")
      (value "600")
      (footprint "eagle-import:1206")
      (libsource (lib "eagle-import") (part "FB_1206"))
    )
    (comp (ref "FB2")
      (value "600")
      (footprint "eagle-import:1206")
      (libsource (lib "eagle-import") (part "FB_1206"))
    )
    (comp (ref "J1")
      (value "2PIN_HEADER")
      (footprint "eagle-import:2MM_2PIN_HEADER")
      (libsource (lib "eagle-import") (part "2PIN_HEADER"))
    )
    (comp (ref "J2")
      (value "2PIN_HEADER")
      (footprint "eagle-import:2MM_2PIN_HEADER")
      (libsource (lib "eagle-import") (part "2PIN_HEADER"))
    )
    (comp (ref "J3")
      (value "2PIN_HEADER")
      (footprint "eagle-import:2MM_2PIN_HEADER")
      (libsource (lib "eagle-import") (part "2PIN_HEADER"))
    )
    (comp (ref "J4")
      (value "2PIN_HEADER")
      (footprint "eagle-import:2MM_2PIN_HEADER")
      (libsource (lib "eagle-import") (part "2PIN_HEADER"))
    )
    (comp (ref "J5")
      (value "2PIN_HEADER")
      (footprint "eagle-import:2MM_2PIN_HEADER")
      (libsource (lib "eagle-import") (part "2PIN_HEADER"))
    )
    (comp (ref "J6")
      (value "2PIN_HEADER")
      (footprint "eagle-import:2MM_2PIN_HEADER")
      (libsource (lib "eagle-import") (part "2PIN_HEADER"))
    )
    (comp (ref "L1")
      (value "4.2uH")
      (footprint "eagle-import:WE-HCI_105023")
      (libsource (lib "eagle-import") (part "INDUCTOR_744325420"))
    )
    (comp (ref "L2")
      (value "1.5uH")
      (footprint "eagle-import:WE-HCI_7030_7040_705023")
      (libsource (lib "eagle-import") (part "INDUCTOR744314150"))
    )
    (comp (ref "M1")
      (value "BSC014N04LSIBSC014N04LSI")
      (footprint "eagle-import:TRANS_BSC014N04LSIATMA1")
      (libsource (lib "eagle-import") (part "BSC014N04LSIBSC014N04LSI"))
    )
    (comp (ref "M2")
      (value "BSC014N04LSIBSC014N04LSI")
      (footprint "eagle-import:TRANS_BSC014N04LSIATMA1")
      (libsource (lib "eagle-import") (part "BSC014N04LSIBSC014N04LSI"))
    )
    (comp (ref "M3")
      (value "BSC093N04LS51")
      (footprint "eagle-import:MOSFET_BSC093N04LSGATMA1")
      (libsource (lib "eagle-import") (part "BSC093N04LS51"))
    )
    (comp (ref "M4")
      (value "BSC093N04LS51")
      (footprint "eagle-import:MOSFET_BSC093N04LSGATMA1")
      (libsource (lib "eagle-import") (part "BSC093N04LS51"))
    )
    (comp (ref "M5")
      (value "BSC014N04LSIBSC014N04LSI")
      (footprint "eagle-import:TRANS_BSC014N04LSIATMA1")
      (libsource (lib "eagle-import") (part "BSC014N04LSIBSC014N04LSI"))
    )
    (comp (ref "M7")
      (value "BSC093N04LS51")
      (footprint "eagle-import:MOSFET_BSC093N04LSGATMA1")
      (libsource (lib "eagle-import") (part "BSC093N04LS51"))
    )
    (comp (ref "R1")
      (value "0.004")
      (footprint "eagle-import:RESC2012X70N")
      (fields
        (field (name "ARROW_PART_NUMBER") "KRL2012E-M-R004-F-T5")
        (field (name "MOUSER_PART_NUMBER") "754-KRL2012EMR004FT5")
      )
      (libsource (lib "eagle-import") (part "KRL2012E-M-R004-F-T5"))
    )
    (comp (ref "R2")
      (value "DNP")
      (footprint "eagle-import:RESC2012X70N")
      (fields
        (field (name "ARROW_PART_NUMBER") "KRL2012E-M-R004-F-T5")
        (field (name "MOUSER_PART_NUMBER") "754-KRL2012EMR004FT5")
      )
      (libsource (lib "eagle-import") (part "KRL2012E-M-R004-F-T5"))
    )
    (comp (ref "R3")
      (value "0.015")
      (footprint "eagle-import:RESC2012X70N")
      (fields
        (field (name "ARROW_PART_NUMBER") "KRL2012E-M-R004-F-T5")
        (field (name "MOUSER_PART_NUMBER") "754-KRL2012EMR004FT5")
      )
      (libsource (lib "eagle-import") (part "KRL2012E-M-R004-F-T5"))
    )
    (comp (ref "R4")
      (value "DNP")
      (footprint "eagle-import:RESC2012X70N")
      (fields
        (field (name "ARROW_PART_NUMBER") "KRL2012E-M-R004-F-T5")
        (field (name "MOUSER_PART_NUMBER") "754-KRL2012EMR004FT5")
      )
      (libsource (lib "eagle-import") (part "KRL2012E-M-R004-F-T5"))
    )
    (comp (ref "R5")
      (value "100K")
      (footprint "eagle-import:0805")
      (libsource (lib "eagle-import") (part "RESISTOR0805-RES"))
    )
    (comp (ref "R6")
      (value "27K")
      (footprint "eagle-import:0805")
      (libsource (lib "eagle-import") (part "RESISTOR0805-RES"))
    )
    (comp (ref "R7")
      (value "75K")
      (footprint "eagle-import:0805")
      (libsource (lib "eagle-import") (part "RESISTOR0805-RES"))
    )
    (comp (ref "R8")
      (value "10K")
      (footprint "eagle-import:0805")
      (libsource (lib "eagle-import") (part "RESISTOR0805-RES"))
    )
    (comp (ref "R9")
      (value "374K")
      (footprint "eagle-import:0805")
      (libsource (lib "eagle-import") (part "RESISTOR0805-RES"))
    )
    (comp (ref "R10")
      (value "165K")
      (footprint "eagle-import:0805")
      (libsource (lib "eagle-import") (part "RESISTOR0805-RES"))
    )
    (comp (ref "R11")
      (value "100K")
      (footprint "eagle-import:0805")
      (libsource (lib "eagle-import") (part "RESISTOR0805-RES"))
    )
    (comp (ref "R12")
      (value "10")
      (footprint "eagle-import:0805")
      (libsource (lib "eagle-import") (part "RESISTOR0805-RES"))
    )
    (comp (ref "R13")
      (value "10")
      (footprint "eagle-import:0805")
      (libsource (lib "eagle-import") (part "RESISTOR0805-RES"))
    )
    (comp (ref "R14")
      (value "10")
      (footprint "eagle-import:0805")
      (libsource (lib "eagle-import") (part "RESISTOR0805-RES"))
    )
    (comp (ref "R15")
      (value "10")
      (footprint "eagle-import:0805")
      (libsource (lib "eagle-import") (part "RESISTOR0805-RES"))
    )
    (comp (ref "R16")
      (value "10")
      (footprint "eagle-import:0805")
      (libsource (lib "eagle-import") (part "RESISTOR0805-RES"))
    )
    (comp (ref "R17")
      (value "10")
      (footprint "eagle-import:0805")
      (libsource (lib "eagle-import") (part "RESISTOR0805-RES"))
    )
    (comp (ref "R18")
      (value "0")
      (footprint "eagle-import:0805")
      (libsource (lib "eagle-import") (part "RESISTOR0805-RES"))
    )
    (comp (ref "R19")
      (value "0")
      (footprint "eagle-import:0805")
      (libsource (lib "eagle-import") (part "RESISTOR0805-RES"))
    )
    (comp (ref "R20")
      (value "0")
      (footprint "eagle-import:0805")
      (libsource (lib "eagle-import") (part "RESISTOR0805-RES"))
    )
    (comp (ref "R21")
      (value "DNP")
      (footprint "eagle-import:0805")
      (libsource (lib "eagle-import") (part "RESISTOR0805-RES"))
    )
    (comp (ref "R22")
      (value "DNP")
      (footprint "eagle-import:0805")
      (libsource (lib "eagle-import") (part "RESISTOR0805-RES"))
    )
    (comp (ref "R23")
      (value "10")
      (footprint "eagle-import:0805")
      (libsource (lib "eagle-import") (part "RESISTOR0805-RES"))
    )
    (comp (ref "R24")
      (value "10")
      (footprint "eagle-import:0805")
      (libsource (lib "eagle-import") (part "RESISTOR0805-RES"))
    )
    (comp (ref "R25")
      (value "DNP")
      (footprint "eagle-import:0805")
      (libsource (lib "eagle-import") (part "RESISTOR0805-RES"))
    )
    (comp (ref "R26")
      (value "DNP")
      (footprint "eagle-import:0805")
      (libsource (lib "eagle-import") (part "RESISTOR0805-RES"))
    )
    (comp (ref "R27")
      (value "DNP")
      (footprint "eagle-import:RESC2012X70N")
      (fields
        (field (name "ARROW_PART_NUMBER") "KRL2012E-M-R004-F-T5")
        (field (name "MOUSER_PART_NUMBER") "754-KRL2012EMR004FT5")
      )
      (libsource (lib "eagle-import") (part "KRL2012E-M-R004-F-T5"))
    )
    (comp (ref "R28")
      (value "DNP")
      (footprint "eagle-import:0805")
      (libsource (lib "eagle-import") (part "RESISTOR0805-RES"))
    )
    (comp (ref "R29")
      (value "DNP")
      (footprint "eagle-import:0805")
      (libsource (lib "eagle-import") (part "RESISTOR0805-RES"))
    )
    (comp (ref "R35")
      (value "0")
      (footprint "eagle-import:1206")
      (libsource (lib "eagle-import") (part "RESISTOR1206"))
    )
    (comp (ref "U1")
      (value "LT8390EFE")
      (footprint "eagle-import:SOP65P640X120-29N")
      (libsource (lib "eagle-import") (part "LT8390EFE"))
    )
    (comp (ref "C47")
      (value "0.1uF")
      (footprint "eagle-import:0805")
      (libsource (lib "eagle-import") (part "CAP0805"))
    )
    (comp (ref "C48")
      (value "1uF")
      (footprint "eagle-import:0805")
      (libsource (lib "eagle-import") (part "CAP0805"))
    )
    (comp (ref "C49")
      (value "10pF")
      (footprint "eagle-import:0805")
      (libsource (lib "eagle-import") (part "CAP0805"))
    )
    (comp (ref "C50")
      (value "47uF")
      (footprint "eagle-import:1210")
      (libsource (lib "eagle-import") (part "CAP1210"))
    )
    (comp (ref "C51")
      (value "4.7uF")
      (footprint "eagle-import:0805")
      (libsource (lib "eagle-import") (part "CAP0805"))
    )
    (comp (ref "C61")
      (value "0.1uF")
      (footprint "eagle-import:0805")
      (libsource (lib "eagle-import") (part "CAP0805"))
    )
    (comp (ref "L5")
      (value "2.2uH")
      (footprint "eagle-import:XFL4030472MEB")
      (fields
        (field (name "ARROW_PART_NUMBER") "XFL4020-222MEC")
        (field (name "MOUSER_PART_NUMBER") "994-XFL4020-222MEC")
      )
      (libsource (lib "eagle-import") (part "XFL4020-222MEC"))
    )
    (comp (ref "R45")
      (value "18.2K")
      (footprint "eagle-import:0805")
      (libsource (lib "eagle-import") (part "RESISTOR0805-RES"))
    )
    (comp (ref "R46")
      (value "49.9K")
      (footprint "eagle-import:0805")
      (libsource (lib "eagle-import") (part "RESISTOR0805-RES"))
    )
    (comp (ref "R47")
      (value "1.0M")
      (footprint "eagle-import:0805")
      (libsource (lib "eagle-import") (part "RESISTOR0805-RES"))
    )
    (comp (ref "R48")
      (value "182K")
      (footprint "eagle-import:0805")
      (libsource (lib "eagle-import") (part "RESISTOR0805-RES"))
    )
    (comp (ref "U4")
      (value "LT8609A")
      (footprint "eagle-import:MSOP-10_MSE")
      (libsource (lib "eagle-import") (part "LT8609A"))
    )
    (comp (ref "C65")
      (value "1uF")
      (footprint "eagle-import:0805")
      (libsource (lib "eagle-import") (part "CAP0805"))
    )
    (comp (ref "C66")
      (value "1uF")
      (footprint "eagle-import:0805")
      (libsource (lib "eagle-import") (part "CAP0805"))
    )
    (comp (ref "C67")
      (value "1uF")
      (footprint "eagle-import:0805")
      (libsource (lib "eagle-import") (part "CAP0805"))
    )
    (comp (ref "C68")
      (value "1uF")
      (footprint "eagle-import:0805")
      (libsource (lib "eagle-import") (part "CAP0805"))
    )
    (comp (ref "C69")
      (value "1uF")
      (footprint "eagle-import:0805")
      (libsource (lib "eagle-import") (part "CAP0805"))
    )
    (comp (ref "U6")
      (value "LTC1477")
      (footprint "eagle-import:SO8")
      (libsource (lib "eagle-import") (part "LTC1477"))
    )
    (comp (ref "U7")
      (value "LTC1477")
      (footprint "eagle-import:SO8")
      (libsource (lib "eagle-import") (part "LTC1477"))
    )
    (comp (ref "U8")
      (value "LTC1477")
      (footprint "eagle-import:SO8")
      (libsource (lib "eagle-import") (part "LTC1477"))
    )
    (comp (ref "U9")
      (value "LTC1477")
      (footprint "eagle-import:SO8")
      (libsource (lib "eagle-import") (part "LTC1477"))
    )
    (comp (ref "U10")
      (value "LTC1477")
      (footprint "eagle-import:SO8")
      (libsource (lib "eagle-import") (part "LTC1477"))
    )
    (comp (ref "C33")
      (value "22uF")
      (footprint "eagle-import:CAPMP7343X430N")
      (libsource (lib "eagle-import") (part "CAP_29172917"))
    )
    (comp (ref "C34")
      (value "4.7uF")
      (footprint "eagle-import:1206")
      (libsource (lib "eagle-import") (part "CAP1206"))
    )
    (comp (ref "C38")
      (value "4.7uF")
      (footprint "eagle-import:1206")
      (libsource (lib "eagle-import") (part "CAP1206"))
    )
    (comp (ref "C39")
      (value "4.7uF")
      (footprint "eagle-import:1206")
      (libsource (lib "eagle-import") (part "CAP1206"))
    )
    (comp (ref "C40")
      (value "0.1uF")
      (footprint "eagle-import:0805")
      (libsource (lib "eagle-import") (part "CAP0805"))
    )
    (comp (ref "C41")
      (value "1uF")
      (footprint "eagle-import:0805")
      (libsource (lib "eagle-import") (part "CAP0805"))
    )
    (comp (ref "FB3")
      (value "330")
      (footprint "eagle-import:0805")
      (libsource (lib "eagle-import") (part "FB_0805"))
    )
    (comp (ref "R99")
      (value "0")
      (footprint "eagle-import:RESC5025X70N")
      (fields
        (field (name "DIGI-KEY_PART_NUMBER") "541-0.0WCT-ND")
        (field (name "MF") "Vishay Dale")
        (field (name "MP") "CRCW20100000Z0EF")
      )
      (libsource (lib "eagle-import") (part "CRCW20100000Z0EF"))
    )
  )
  (nets
    (net (code "1") (name "+3V3") (class "Default")
      (node (ref "R30") (pin "2") (pinfunction "2_2") (pintype "passive"))
      (node (ref "R36") (pin "2") (pinfunction "2_2") (pintype "passive"))
      (node (ref "R37") (pin "2") (pinfunction "2_2") (pintype "passive"))
      (node (ref "R38") (pin "2") (pinfunction "2_2") (pintype "passive"))
      (node (ref "R55") (pin "2") (pinfunction "2_2") (pintype "passive"))
      (node (ref "R58") (pin "2") (pinfunction "2_2") (pintype "passive"))
      (node (ref "TB1") (pin "P17") (pinfunction "+3V3_P17") (pintype "bidirectional"))
      (node (ref "U2") (pin "8") (pinfunction "VCC_8") (pintype "bidirectional"))
    )
    (net (code "2") (name "3V3_BUS") (class "Default")
      (node (ref "C54") (pin "2") (pinfunction "2_2") (pintype "passive"))
      (node (ref "C55") (pin "1") (pinfunction "1_1") (pintype "passive"))
      (node (ref "C56") (pin "1") (pinfunction "1_1") (pintype "passive"))
      (node (ref "H1") (pin "2.27") (pinfunction "2.27_2.27") (pintype "bidirectional"))
      (node (ref "H1") (pin "2.28") (pinfunction "2.28_2.28") (pintype "bidirectional"))
      (node (ref "L6") (pin "2") (pinfunction "2_2") (pintype "bidirectional"))
      (node (ref "R52") (pin "2") (pinfunction "2_2") (pintype "passive"))
      (node (ref "R53") (pin "2") (pinfunction "2_2") (pintype "passive"))
      (node (ref "U9") (pin "2") (pinfunction "VIN1_2") (pintype "bidirectional"))
      (node (ref "U9") (pin "3") (pinfunction "VINS_3") (pintype "bidirectional"))
      (node (ref "U9") (pin "7") (pinfunction "VIN2_7") (pintype "bidirectional"))
    )
    (net (code "3") (name "5V_BUS") (class "Default")
      (node (ref "C49") (pin "2") (pinfunction "2_2") (pintype "passive"))
      (node (ref "C50") (pin "1") (pinfunction "1_1") (pintype "passive"))
      (node (ref "C51") (pin "1") (pinfunction "1_1") (pintype "passive"))
      (node (ref "C57") (pin "1") (pinfunction "1_1") (pintype "passive"))
      (node (ref "H1") (pin "2.25") (pinfunction "2.25_2.25") (pintype "bidirectional"))
      (node (ref "H1") (pin "2.26") (pinfunction "2.26_2.26") (pintype "bidirectional"))
      (node (ref "L5") (pin "2") (pinfunction "2_2") (pintype "bidirectional"))
      (node (ref "R46") (pin "2") (pinfunction "2_2") (pintype "passive"))
      (node (ref "R47") (pin "2") (pinfunction "2_2") (pintype "passive"))
      (node (ref "TB1") (pin "P30") (pinfunction "VIN_P30") (pintype "bidirectional"))
      (node (ref "U11") (pin "8") (pinfunction "VDD_8") (pintype "bidirectional"))
      (node (ref "U6") (pin "2") (pinfunction "VIN1_2") (pintype "bidirectional"))
      (node (ref "U6") (pin "3") (pinfunction "VINS_3") (pintype "bidirectional"))
      (node (ref "U6") (pin "7") (pinfunction "VIN2_7") (pintype "bidirectional"))
      (node (ref "U7") (pin "2") (pinfunction "VIN1_2") (pintype "bidirectional"))
      (node (ref "U7") (pin "3") (pinfunction "VINS_3") (pintype "bidirectional"))
      (node (ref "U7") (pin "7") (pinfunction "VIN2_7") (pintype "bidirectional"))
      (node (ref "U8") (pin "2") (pinfunction "VIN1_2") (pintype "bidirectional"))
      (node (ref "U8") (pin "3") (pinfunction "VINS_3") (pintype "bidirectional"))
      (node (ref "U8") (pin "7") (pinfunction "VIN2_7") (pintype "bidirectional"))
    )
    (net (code "4") (name "5V_USB_CHG") (class "Default")
      (node (ref "D7") (pin "A") (pinfunction "A_A") (pintype "passive"))
      (node (ref "H1") (pin "1.32") (pinfunction "1.32_1.32") (pintype "bidirectional"))
    )
    (net (code "5") (name "BCR_OUT") (class "Default")
      (node (ref "D11") (pin "C") (pinfunction "C_C") (pintype "passive"))
      (node (ref "H1") (pin "2.41") (pinfunction "2.41_2.41") (pintype "bidirectional"))
      (node (ref "H1") (pin "2.42") (pinfunction "2.42_2.42") (pintype "bidirectional"))
      (node (ref "H1") (pin "2.43") (pinfunction "2.43_2.43") (pintype "bidirectional"))
      (node (ref "H1") (pin "2.44") (pinfunction "2.44_2.44") (pintype "bidirectional"))
    )
    (net (code "6") (name "BUS_EN") (class "Default")
      (node (ref "C63") (pin "1") (pinfunction "1_1") (pintype "passive"))
      (node (ref "R61") (pin "2") (pinfunction "2_2") (pintype "passive"))
      (node (ref "U13") (pin "2") (pinfunction "VOUT_2") (pintype "power_in"))
      (node (ref "U13") (pin "3") (pinfunction "VOUT_3") (pintype "power_in"))
      (node (ref "U4") (pin "10") (pinfunction "EN_10") (pintype "bidirectional"))
      (node (ref "U5") (pin "10") (pinfunction "EN_10") (pintype "bidirectional"))
    )
    (net (code "7") (name "COM") (class "Default")
      (node (ref "C2") (pin "1") (pinfunction "1_1") (pintype "passive"))
      (node (ref "C26") (pin "2") (pinfunction "2_2") (pintype "passive"))
      (node (ref "C3") (pin "1") (pinfunction "1_1") (pintype "passive"))
      (node (ref "C5") (pin "2") (pinfunction "2_2") (pintype "passive"))
      (node (ref "C6") (pin "2") (pinfunction "2_2") (pintype "passive"))
      (node (ref "R10") (pin "1") (pinfunction "1_1") (pintype "passive"))
      (node (ref "R21") (pin "1") (pinfunction "1_1") (pintype "passive"))
      (node (ref "R35") (pin "1") (pinfunction "1_1") (pintype "passive"))
      (node (ref "R5") (pin "1") (pinfunction "1_1") (pintype "passive"))
      (node (ref "U1") (pin "10") (pinfunction "TEST_10") (pintype "bidirectional"))
    )
    (net (code "8") (name "CSKB_TO_EPS_RX") (class "Default")
      (node (ref "H1") (pin "1.51") (pinfunction "1.51_1.51") (pintype "bidirectional"))
      (node (ref "TB1") (pin "P2") (pinfunction "RX_P2") (pintype "bidirectional"))
    )
    (net (code "9") (name "EN_LT8390") (class "Default")
      (node (ref "R10") (pin "2") (pinfunction "2_2") (pintype "passive"))
      (node (ref "R9") (pin "1") (pinfunction "1_1") (pintype "passive"))
      (node (ref "U1") (pin "9") (pinfunction "EN_9") (pintype "bidirectional"))
    )
    (net (code "10") (name "EPS_SCL_TO_BUFFER") (class "Default")
      (node (ref "R36") (pin "1") (pinfunction "1_1") (pintype "passive"))
      (node (ref "TB1") (pin "P24") (pinfunction "I2C_SCL_P24") (pintype "bidirectional"))
      (node (ref "U2") (pin "3") (pinfunction "SCL_DEV_3") (pintype "bidirectional"))
    )
    (net (code "11") (name "EPS_SDA_TO_BUFFER") (class "Default")
      (node (ref "R30") (pin "1") (pinfunction "1_1") (pintype "passive"))
      (node (ref "TB1") (pin "P23") (pinfunction "I2C_SDA_P23") (pintype "bidirectional"))
      (node (ref "U2") (pin "6") (pinfunction "SDA_DEV_6") (pintype "bidirectional"))
    )
    (net (code "12") (name "EPS_TO_WDI") (class "Default")
      (node (ref "J10") (pin "1") (pinfunction "1_1") (pintype "passive"))
      (node (ref "TB1") (pin "P13") (pinfunction "D10_P13") (pintype "bidirectional"))
      (node (ref "U12") (pin "6") (pinfunction "WDI_6") (pintype "bidirectional"))
    )
    (net (code "13") (name "EPS_TX_TO_CSKB") (class "Default")
      (node (ref "H1") (pin "1.49") (pinfunction "1.49_1.49") (pintype "bidirectional"))
      (node (ref "TB1") (pin "P1") (pinfunction "TX_P1") (pintype "bidirectional"))
    )
    (net (code "14") (name "GND") (class "Default")
      (node (ref "C1") (pin "2") (pinfunction "2_2") (pintype "passive"))
      (node (ref "C10") (pin "2") (pinfunction "2_2") (pintype "passive"))
      (node (ref "C11") (pin "2") (pinfunction "2_2") (pintype "passive"))
      (node (ref "C12") (pin "2") (pinfunction "2_2") (pintype "passive"))
      (node (ref "C13") (pin "2") (pinfunction "2_2") (pintype "passive"))
      (node (ref "C14") (pin "2") (pinfunction "2_2") (pintype "passive"))
      (node (ref "C15") (pin "2") (pinfunction "2_2") (pintype "passive"))
      (node (ref "C16") (pin "2") (pinfunction "2_2") (pintype "passive"))
      (node (ref "C17") (pin "2") (pinfunction "2_2") (pintype "passive"))
      (node (ref "C18") (pin "2") (pinfunction "2_2") (pintype "passive"))
      (node (ref "C19") (pin "2") (pinfunction "2_2") (pintype "passive"))
      (node (ref "C20") (pin "2") (pinfunction "2_2") (pintype "passive"))
      (node (ref "C21") (pin "2") (pinfunction "2_2") (pintype "passive"))
      (node (ref "C22") (pin "2") (pinfunction "2_2") (pintype "passive"))
      (node (ref "C23") (pin "2") (pinfunction "2_2") (pintype "passive"))
      (node (ref "C24") (pin "2") (pinfunction "2_2") (pintype "passive"))
      (node (ref "C29") (pin "2") (pinfunction "2_2") (pintype "passive"))
      (node (ref "C31") (pin "2") (pinfunction "2_2") (pintype "passive"))
      (node (ref "C32") (pin "2") (pinfunction "2_2") (pintype "passive"))
      (node (ref "C33") (pin "2") (pinfunction "2_2") (pintype "passive"))
      (node (ref "C34") (pin "2") (pinfunction "2_2") (pintype "passive"))
      (node (ref "C35") (pin "2") (pinfunction "2_2") (pintype "passive"))
      (node (ref "C36") (pin "1") (pinfunction "1_1") (pintype "passive"))
      (node (ref "C37") (pin "2") (pinfunction "2_2") (pintype "passive"))
      (node (ref "C38") (pin "2") (pinfunction "2_2") (pintype "passive"))
      (node (ref "C39") (pin "2") (pinfunction "2_2") (pintype "passive"))
      (node (ref "C4") (pin "1") (pinfunction "1_1") (pintype "passive"))
      (node (ref "C40") (pin "2") (pinfunction "2_2") (pintype "passive"))
      (node (ref "C41") (pin "2") (pinfunction "2_2") (pintype "passive"))
      (node (ref "C42") (pin "2") (pinfunction "2_2") (pintype "passive"))
      (node (ref "C43") (pin "2") (pinfunction "2_2") (pintype "passive"))
      (node (ref "C45") (pin "2") (pinfunction "2_2") (pintype "passive"))
      (node (ref "C46") (pin "2") (pinfunction "2_2") (pintype "passive"))
      (node (ref "C47") (pin "2") (pinfunction "2_2") (pintype "passive"))
      (node (ref "C48") (pin "2") (pinfunction "2_2") (pintype "passive"))
      (node (ref "C50") (pin "2") (pinfunction "2_2") (pintype "passive"))
      (node (ref "C51") (pin "2") (pinfunction "2_2") (pintype "passive"))
      (node (ref "C52") (pin "2") (pinfunction "2_2") (pintype "passive"))
      (node (ref "C53") (pin "2") (pinfunction "2_2") (pintype "passive"))
      (node (ref "C55") (pin "2") (pinfunction "2_2") (pintype "passive"))
      (node (ref "C56") (pin "2") (pinfunction "2_2") (pintype "passive"))
      (node (ref "C57") (pin "2") (pinfunction "2_2") (pintype "passive"))
      (node (ref "C58") (pin "2") (pinfunction "2_2") (pintype "passive"))
      (node (ref "C59") (pin "2") (pinfunction "2_2") (pintype "passive"))
      (node (ref "C65") (pin "2") (pinfunction "2_2") (pintype "passive"))
      (node (ref "C66") (pin "2") (pinfunction "2_2") (pintype "passive"))
      (node (ref "C67") (pin "2") (pinfunction "2_2") (pintype "passive"))
      (node (ref "C68") (pin "2") (pinfunction "2_2") (pintype "passive"))
      (node (ref "C69") (pin "2") (pinfunction "2_2") (pintype "passive"))
      (node (ref "C9") (pin "2") (pinfunction "2_2") (pintype "passive"))
      (node (ref "D10") (pin "A") (pinfunction "A_A") (pintype "passive"))
      (node (ref "D8") (pin "A") (pinfunction "A_A") (pintype "passive"))
      (node (ref "H1") (pin "2.14") (pinfunction "2.14_2.14") (pintype "bidirectional"))
      (node (ref "H1") (pin "2.17") (pinfunction "2.17_2.17") (pintype "bidirectional"))
      (node (ref "H1") (pin "2.21") (pinfunction "2.21_2.21") (pintype "bidirectional"))
      (node (ref "H1") (pin "2.22") (pinfunction "2.22_2.22") (pintype "bidirectional"))
      (node (ref "H1") (pin "2.29") (pinfunction "2.29_2.29") (pintype "bidirectional"))
      (node (ref "H1") (pin "2.30") (pinfunction "2.30_2.30") (pintype "bidirectional"))
      (node (ref "H1") (pin "2.32") (pinfunction "2.32_2.32") (pintype "bidirectional"))
      (node (ref "H1") (pin "2.47") (pinfunction "2.47_2.47") (pintype "bidirectional"))
      (node (ref "H1") (pin "2.48") (pinfunction "2.48_2.48") (pintype "bidirectional"))
      (node (ref "H1") (pin "2.9") (pinfunction "2.9_2.9") (pintype "bidirectional"))
      (node (ref "J1") (pin "2") (pinfunction "2_2") (pintype "bidirectional"))
      (node (ref "J2") (pin "2") (pinfunction "2_2") (pintype "bidirectional"))
      (node (ref "J3") (pin "2") (pinfunction "2_2") (pintype "bidirectional"))
      (node (ref "J4") (pin "2") (pinfunction "2_2") (pintype "bidirectional"))
      (node (ref "J5") (pin "2") (pinfunction "2_2") (pintype "bidirectional"))
      (node (ref "J6") (pin "2") (pinfunction "2_2") (pintype "bidirectional"))
      (node (ref "M2") (pin "1") (pinfunction "S_1") (pintype "passive"))
      (node (ref "M3") (pin "1") (pinfunction "S_1") (pintype "passive"))
      (node (ref "M3") (pin "2") (pinfunction "S_2") (pintype "passive"))
      (node (ref "M3") (pin "3") (pinfunction "S_3") (pintype "passive"))
      (node (ref "M7") (pin "1") (pinfunction "S_1") (pintype "passive"))
      (node (ref "M7") (pin "2") (pinfunction "S_2") (pintype "passive"))
      (node (ref "M7") (pin "3") (pinfunction "S_3") (pintype "passive"))
      (node (ref "R31") (pin "1") (pinfunction "1_1") (pintype "passive"))
      (node (ref "R32") (pin "1") (pinfunction "1_1") (pintype "passive"))
      (node (ref "R33") (pin "1") (pinfunction "1_1") (pintype "passive"))
      (node (ref "R34") (pin "1") (pinfunction "1_1") (pintype "passive"))
      (node (ref "R35") (pin "2") (pinfunction "2_2") (pintype "passive"))
      (node (ref "R39") (pin "1") (pinfunction "1_1") (pintype "passive"))
      (node (ref "R40") (pin "1") (pinfunction "1_1") (pintype "passive"))
      (node (ref "R45") (pin "1") (pinfunction "1_1") (pintype "passive"))
      (node (ref "R48") (pin "1") (pinfunction "1_1") (pintype "passive"))
      (node (ref "R51") (pin "1") (pinfunction "1_1") (pintype "passive"))
      (node (ref "R54") (pin "1") (pinfunction "1_1") (pintype "passive"))
      (node (ref "R56") (pin "1") (pinfunction "1_1") (pintype "passive"))
      (node (ref "R61") (pin "1") (pinfunction "1_1") (pintype "passive"))
      (node (ref "R8") (pin "1") (pinfunction "1_1") (pintype "passive"))
      (node (ref "TB1") (pin "P29") (pinfunction "GND_P29") (pintype "bidirectional"))
      (node (ref "TB1") (pin "P4") (pinfunction "GND_P4") (pintype "bidirectional"))
      (node (ref "U1") (pin "22") (pinfunction "SYNC_22") (pintype "bidirectional"))
      (node (ref "U1") (pin "29") (pinfunction "GND_29") (pintype "bidirectional"))
      (node (ref "U10") (pin "5") (pinfunction "GND_5") (pintype "bidirectional"))
      (node (ref "U11") (pin "7") (pinfunction "GND_7") (pintype "bidirectional"))
      (node (ref "U12") (pin "5") (pinfunction "GND_5") (pintype "bidirectional"))
      (node (ref "U13") (pin "1") (pinfunction "GND_1") (pintype "power_in"))
      (node (ref "U2") (pin "4") (pinfunction "GND_4") (pintype "bidirectional"))
      (node (ref "U3") (pin "11") (pinfunction "GND_11") (pintype "bidirectional"))
      (node (ref "U3") (pin "5") (pinfunction "SYNC_5") (pintype "bidirectional"))
      (node (ref "U4") (pin "11") (pinfunction "GND_11") (pintype "bidirectional"))
      (node (ref "U4") (pin "5") (pinfunction "SYNC_5") (pintype "bidirectional"))
      (node (ref "U5") (pin "11") (pinfunction "GND_11") (pintype "bidirectional"))
      (node (ref "U5") (pin "5") (pinfunction "SYNC_5") (pintype "bidirectional"))
      (node (ref "U6") (pin "5") (pinfunction "GND_5") (pintype "bidirectional"))
      (node (ref "U7") (pin "5") (pinfunction "GND_5") (pintype "bidirectional"))
      (node (ref "U8") (pin "5") (pinfunction "GND_5") (pintype "bidirectional"))
      (node (ref "U9") (pin "5") (pinfunction "GND_5") (pintype "bidirectional"))
    )
    (net (code "15") (name "I2C_EN") (class "Default")
      (node (ref "TB1") (pin "P5") (pinfunction "D2_P5") (pintype "bidirectional"))
      (node (ref "U2") (pin "1") (pinfunction "EN_1") (pintype "bidirectional"))
    )
    (net (code "16") (name "I2C_SCL") (class "Default")
      (node (ref "H1") (pin "1.43") (pinfunction "1.43_1.43") (pintype "bidirectional"))
      (node (ref "U2") (pin "2") (pinfunction "SCL_BUS_2") (pintype "bidirectional"))
    )
    (net (code "17") (name "I2C_SDA") (class "Default")
      (node (ref "H1") (pin "1.41") (pinfunction "1.41_1.41") (pintype "bidirectional"))
      (node (ref "U2") (pin "7") (pinfunction "SDA_BUS_7") (pintype "bidirectional"))
    )
    (net (code "18") (name "ISN_LT8390") (class "Default")
      (node (ref "C23") (pin "1") (pinfunction "1_1") (pintype "passive"))
      (node (ref "C24") (pin "1") (pinfunction "1_1") (pintype "passive"))
      (node (ref "C25") (pin "2") (pinfunction "2_2") (pintype "passive"))
      (node (ref "C27") (pin "2") (pinfunction "2_2") (pintype "passive"))
      (node (ref "D10") (pin "C") (pinfunction "C_C") (pintype "passive"))
      (node (ref "FB1") (pin "1") (pinfunction "1_1") (pintype "bidirectional"))
      (node (ref "FB2") (pin "1") (pinfunction "1_1") (pintype "bidirectional"))
      (node (ref "R13") (pin "1") (pinfunction "1_1") (pintype "passive"))
      (node (ref "R13") (pin "2") (pinfunction "2_2") (pintype "passive"))
      (node (ref "R18") (pin "2") (pinfunction "2_2") (pintype "passive"))
      (node (ref "R25") (pin "1") (pinfunction "1_1") (pintype "passive"))
      (node (ref "R3") (pin "2") (pinfunction "2_2") (pintype "passive"))
      (node (ref "R4") (pin "2") (pinfunction "2_2") (pintype "passive"))
      (node (ref "U1") (pin "15") (pinfunction "ISN_15") (pintype "bidirectional"))
    )
    (net (code "19") (name "ISP_LT8390") (class "Default")
      (node (ref "C13") (pin "1") (pinfunction "1_1") (pintype "passive"))
      (node (ref "C14") (pin "1") (pinfunction "1_1") (pintype "passive"))
      (node (ref "C15") (pin "1") (pinfunction "1_1") (pintype "passive"))
      (node (ref "C16") (pin "1") (pinfunction "1_1") (pintype "passive"))
      (node (ref "C25") (pin "1") (pinfunction "1_1") (pintype "passive"))
      (node (ref "C27") (pin "1") (pinfunction "1_1") (pintype "passive"))
      (node (ref "C36") (pin "2") (pinfunction "2_2") (pintype "passive"))
      (node (ref "C37") (pin "1") (pinfunction "1_1") (pintype "passive"))
      (node (ref "C4") (pin "2") (pinfunction "2_2") (pintype "passive"))
      (node (ref "D9") (pin "C") (pinfunction "C_C") (pintype "passive"))
      (node (ref "M4") (pin "5") (pinfunction "D_5") (pintype "passive"))
      (node (ref "R12") (pin "1") (pinfunction "1_1") (pintype "passive"))
      (node (ref "R12") (pin "2") (pinfunction "2_2") (pintype "passive"))
      (node (ref "R26") (pin "1") (pinfunction "1_1") (pintype "passive"))
      (node (ref "R3") (pin "1") (pinfunction "1_1") (pintype "passive"))
      (node (ref "R4") (pin "1") (pinfunction "1_1") (pintype "passive"))
      (node (ref "U1") (pin "14") (pinfunction "ISP_14") (pintype "bidirectional"))
      (node (ref "U1") (pin "24") (pinfunction "VOUT_24") (pintype "bidirectional"))
    )
    (net (code "20") (name "Net-(C6-Pad1)") (class "Default")
      (node (ref "C6") (pin "1") (pinfunction "1_1") (pintype "passive"))
      (node (ref "R6") (pin "1") (pinfunction "1_1") (pintype "passive"))
    )
    (net (code "21") (name "Net-(C29-Pad1)") (class "Default")
      (node (ref "C29") (pin "1") (pinfunction "1_1") (pintype "passive"))
      (node (ref "R28") (pin "1") (pinfunction "1_1") (pintype "passive"))
    )
    (net (code "22") (name "Net-(C30-Pad1)") (class "Default")
      (node (ref "C30") (pin "1") (pinfunction "1_1") (pintype "passive"))
      (node (ref "R29") (pin "1") (pinfunction "1_1") (pintype "passive"))
    )
    (net (code "23") (name "Net-(C32-Pad1)") (class "Default")
      (node (ref "C32") (pin "1") (pinfunction "1_1") (pintype "passive"))
      (node (ref "D11") (pin "A") (pinfunction "A_A") (pintype "passive"))
      (node (ref "FB1") (pin "2") (pinfunction "2_2") (pintype "bidirectional"))
      (node (ref "FB2") (pin "2") (pinfunction "2_2") (pintype "bidirectional"))
    )
    (net (code "24") (name "Net-(C38-Pad1)") (class "Default")
      (node (ref "C38") (pin "1") (pinfunction "1_1") (pintype "passive"))
      (node (ref "FB3") (pin "2") (pinfunction "2_2") (pintype "bidirectional"))
      (node (ref "R99") (pin "1") (pinfunction "1_1") (pintype "passive"))
    )
    (net (code "25") (name "Net-(D1-PadA)") (class "Default")
      (node (ref "D1") (pin "A") (pinfunction "A_A") (pintype "passive"))
      (node (ref "J1") (pin "1") (pinfunction "1_1") (pintype "bidirectional"))
    )
    (net (code "26") (name "Net-(D2-PadA)") (class "Default")
      (node (ref "D2") (pin "A") (pinfunction "A_A") (pintype "passive"))
      (node (ref "J2") (pin "1") (pinfunction "1_1") (pintype "bidirectional"))
    )
    (net (code "27") (name "Net-(D3-PadA)") (class "Default")
      (node (ref "D3") (pin "A") (pinfunction "A_A") (pintype "passive"))
      (node (ref "J3") (pin "1") (pinfunction "1_1") (pintype "bidirectional"))
    )
    (net (code "28") (name "Net-(D4-PadA)") (class "Default")
      (node (ref "D4") (pin "A") (pinfunction "A_A") (pintype "passive"))
      (node (ref "J4") (pin "1") (pinfunction "1_1") (pintype "bidirectional"))
    )
    (net (code "29") (name "Net-(D5-PadA)") (class "Default")
      (node (ref "D5") (pin "A") (pinfunction "A_A") (pintype "passive"))
      (node (ref "J5") (pin "1") (pinfunction "1_1") (pintype "bidirectional"))
    )
    (net (code "30") (name "Net-(D6-PadA)") (class "Default")
      (node (ref "D6") (pin "A") (pinfunction "A_A") (pintype "passive"))
      (node (ref "J6") (pin "1") (pinfunction "1_1") (pintype "bidirectional"))
    )
    (net (code "31") (name "Net-(H1-PadP1)") (class "Default")
      (node (ref "H1") (pin "P1") (pinfunction "P1_P1") (pintype "bidirectional"))
      (node (ref "R31") (pin "2") (pinfunction "2_2") (pintype "passive"))
    )
    (net (code "32") (name "Net-(H1-PadP2)") (class "Default")
      (node (ref "H1") (pin "P2") (pinfunction "P2_P2") (pintype "bidirectional"))
      (node (ref "R32") (pin "2") (pinfunction "2_2") (pintype "passive"))
    )
    (net (code "33") (name "Net-(H1-PadP3)") (class "Default")
      (node (ref "H1") (pin "P3") (pinfunction "P3_P3") (pintype "bidirectional"))
      (node (ref "R33") (pin "2") (pinfunction "2_2") (pintype "passive"))
    )
    (net (code "34") (name "Net-(H1-PadP4)") (class "Default")
      (node (ref "H1") (pin "P4") (pinfunction "P4_P4") (pintype "bidirectional"))
      (node (ref "R34") (pin "2") (pinfunction "2_2") (pintype "passive"))
    )
    (net (code "35") (name "Net-(M1-G)") (class "Default")
      (node (ref "M1") (pin "4") (pinfunction "G_4") (pintype "passive"))
      (node (ref "M5") (pin "4") (pinfunction "G_4") (pintype "passive"))
      (node (ref "R17") (pin "2") (pinfunction "2_2") (pintype "passive"))
    )
    (net (code "36") (name "Net-(M1-S)") (class "Default")
      (node (ref "C28") (pin "1") (pinfunction "1_1") (pintype "passive"))
      (node (ref "C30") (pin "2") (pinfunction "2_2") (pintype "passive"))
      (node (ref "C7") (pin "2") (pinfunction "2_2") (pintype "passive"))
      (node (ref "D8") (pin "C") (pinfunction "C_C") (pintype "passive"))
      (node (ref "M1") (pin "1") (pinfunction "S_1") (pintype "passive"))
      (node (ref "M2") (pin "8") (pinfunction "D_8") (pintype "passive"))
      (node (ref "M5") (pin "1") (pinfunction "S_1") (pintype "passive"))
      (node (ref "R1") (pin "1") (pinfunction "1_1") (pintype "passive"))
      (node (ref "R2") (pin "1") (pinfunction "1_1") (pintype "passive"))
      (node (ref "R23") (pin "1") (pinfunction "1_1") (pintype "passive"))
      (node (ref "R23") (pin "2") (pinfunction "2_2") (pintype "passive"))
      (node (ref "U1") (pin "3") (pinfunction "SW1_3") (pintype "bidirectional"))
      (node (ref "U1") (pin "5") (pinfunction "LSP_5") (pintype "bidirectional"))
    )
    (net (code "37") (name "Net-(M2-G)") (class "Default")
      (node (ref "M2") (pin "4") (pinfunction "G_4") (pintype "passive"))
      (node (ref "R16") (pin "2") (pinfunction "2_2") (pintype "passive"))
    )
    (net (code "38") (name "Net-(M3-D)") (class "Default")
      (node (ref "C8") (pin "1") (pinfunction "1_1") (pintype "passive"))
      (node (ref "D9") (pin "A") (pinfunction "A_A") (pintype "passive"))
      (node (ref "L1") (pin "2") (pinfunction "2_2") (pintype "bidirectional"))
      (node (ref "M3") (pin "5") (pinfunction "D_5") (pintype "passive"))
      (node (ref "M4") (pin "1") (pinfunction "S_1") (pintype "passive"))
      (node (ref "M4") (pin "2") (pinfunction "S_2") (pintype "passive"))
      (node (ref "M4") (pin "3") (pinfunction "S_3") (pintype "passive"))
      (node (ref "M7") (pin "5") (pinfunction "D_5") (pintype "passive"))
      (node (ref "R28") (pin "2") (pinfunction "2_2") (pintype "passive"))
      (node (ref "U1") (pin "26") (pinfunction "SW2_26") (pintype "bidirectional"))
    )
    (net (code "39") (name "Net-(M3-G)") (class "Default")
      (node (ref "M3") (pin "4") (pinfunction "G_4") (pintype "passive"))
      (node (ref "M7") (pin "4") (pinfunction "G_4") (pintype "passive"))
      (node (ref "R15") (pin "2") (pinfunction "2_2") (pintype "passive"))
    )
    (net (code "40") (name "Net-(M4-G)") (class "Default")
      (node (ref "M4") (pin "4") (pinfunction "G_4") (pintype "passive"))
      (node (ref "R14") (pin "2") (pinfunction "2_2") (pintype "passive"))
    )
    (net (code "41") (name "Net-(R18-Pad1)") (class "Default")
      (node (ref "R18") (pin "1") (pinfunction "1_1") (pintype "passive"))
      (node (ref "R7") (pin "2") (pinfunction "2_2") (pintype "passive"))
    )
    (net (code "42") (name "Net-(U1-BG1)") (class "Default")
      (node (ref "R16") (pin "1") (pinfunction "1_1") (pintype "passive"))
      (node (ref "U1") (pin "1") (pinfunction "BG1_1") (pintype "bidirectional"))
    )
    (net (code "43") (name "Net-(U1-BG2)") (class "Default")
      (node (ref "R15") (pin "1") (pinfunction "1_1") (pintype "passive"))
      (node (ref "U1") (pin "28") (pinfunction "BG2_28") (pintype "bidirectional"))
    )
    (net (code "44") (name "Net-(U1-BST1)") (class "Default")
      (node (ref "C7") (pin "1") (pinfunction "1_1") (pintype "passive"))
      (node (ref "U1") (pin "2") (pinfunction "BST1_2") (pintype "bidirectional"))
    )
    (net (code "45") (name "Net-(U1-BST2)") (class "Default")
      (node (ref "C8") (pin "2") (pinfunction "2_2") (pintype "passive"))
      (node (ref "U1") (pin "27") (pinfunction "BST2_27") (pintype "bidirectional"))
    )
    (net (code "46") (name "Net-(U1-CTRL)") (class "Default")
      (node (ref "R19") (pin "1") (pinfunction "1_1") (pintype "passive"))
      (node (ref "R21") (pin "2") (pinfunction "2_2") (pintype "passive"))
      (node (ref "U1") (pin "13") (pinfunction "CTRL_13") (pintype "bidirectional"))
    )
    (net (code "47") (name "Net-(U1-FB)") (class "Default")
      (node (ref "R7") (pin "1") (pinfunction "1_1") (pintype "passive"))
      (node (ref "R8") (pin "2") (pinfunction "2_2") (pintype "passive"))
      (node (ref "U1") (pin "19") (pinfunction "FB_19") (pintype "bidirectional"))
    )
    (net (code "48") (name "Net-(U1-INTVCC)") (class "Default")
      (node (ref "C2") (pin "2") (pinfunction "2_2") (pintype "passive"))
      (node (ref "R11") (pin "2") (pinfunction "2_2") (pintype "passive"))
      (node (ref "U1") (pin "8") (pinfunction "INTVCC_8") (pintype "bidirectional"))
    )
    (net (code "49") (name "Net-(U1-LOADEN)") (class "Default")
      (node (ref "R20") (pin "2") (pinfunction "2_2") (pintype "passive"))
      (node (ref "U1") (pin "11") (pinfunction "LOADEN_11") (pintype "bidirectional"))
    )
    (net (code "50") (name "Net-(U1-LSN)") (class "Default")
      (node (ref "C28") (pin "2") (pinfunction "2_2") (pintype "passive"))
      (node (ref "L1") (pin "1") (pinfunction "1_1") (pintype "bidirectional"))
      (node (ref "R1") (pin "2") (pinfunction "2_2") (pintype "passive"))
      (node (ref "R2") (pin "2") (pinfunction "2_2") (pintype "passive"))
      (node (ref "R24") (pin "1") (pinfunction "1_1") (pintype "passive"))
      (node (ref "R24") (pin "2") (pinfunction "2_2") (pintype "passive"))
      (node (ref "U1") (pin "6") (pinfunction "LSN_6") (pintype "bidirectional"))
    )
    (net (code "51") (name "Net-(U1-PGOOD)") (class "Default")
      (node (ref "R11") (pin "1") (pinfunction "1_1") (pintype "passive"))
      (node (ref "U1") (pin "17") (pinfunction "PGOOD_17") (pintype "bidirectional"))
    )
    (net (code "52") (name "Net-(U1-RT)") (class "Default")
      (node (ref "R5") (pin "2") (pinfunction "2_2") (pintype "passive"))
      (node (ref "U1") (pin "21") (pinfunction "RT_21") (pintype "bidirectional"))
    )
    (net (code "53") (name "Net-(U1-SS)") (class "Default")
      (node (ref "C5") (pin "1") (pinfunction "1_1") (pintype "passive"))
      (node (ref "R22") (pin "2") (pinfunction "2_2") (pintype "passive"))
      (node (ref "U1") (pin "18") (pinfunction "SS_18") (pintype "bidirectional"))
    )
    (net (code "54") (name "Net-(U1-TG1)") (class "Default")
      (node (ref "R17") (pin "1") (pinfunction "1_1") (pintype "passive"))
      (node (ref "U1") (pin "4") (pinfunction "TG1_4") (pintype "bidirectional"))
    )
    (net (code "55") (name "Net-(U1-TG2)") (class "Default")
      (node (ref "R14") (pin "1") (pinfunction "1_1") (pintype "passive"))
      (node (ref "U1") (pin "25") (pinfunction "TG2_25") (pintype "bidirectional"))
    )
    (net (code "56") (name "Net-(U1-VC)") (class "Default")
      (node (ref "C26") (pin "1") (pinfunction "1_1") (pintype "passive"))
      (node (ref "R6") (pin "2") (pinfunction "2_2") (pintype "passive"))
      (node (ref "U1") (pin "20") (pinfunction "VC_20") (pintype "bidirectional"))
    )
    (net (code "57") (name "Net-(U3-BST)") (class "Default")
      (node (ref "C60") (pin "1") (pinfunction "1_1") (pintype "passive"))
      (node (ref "U3") (pin "1") (pinfunction "BST_1") (pintype "bidirectional"))
    )
    (net (code "58") (name "Net-(U3-FB)") (class "Default")
      (node (ref "C44") (pin "1") (pinfunction "1_1") (pintype "passive"))
      (node (ref "R40") (pin "2") (pinfunction "2_2") (pintype "passive"))
      (node (ref "R41") (pin "1") (pinfunction "1_1") (pintype "passive"))
      (node (ref "U3") (pin "6") (pinfunction "FB_6") (pintype "bidirectional"))
    )
    (net (code "59") (name "Net-(U3-INTVCC)") (class "Default")
      (node (ref "C42") (pin "1") (pinfunction "1_1") (pintype "passive"))
      (node (ref "U3") (pin "3") (pinfunction "INTVCC_3") (pintype "bidirectional"))
    )
    (net (code "60") (name "Net-(U3-PG)") (class "Default")
      (node (ref "R42") (pin "1") (pinfunction "1_1") (pintype "passive"))
      (node (ref "U3") (pin "8") (pinfunction "PG_8") (pintype "bidirectional"))
    )
    (net (code "61") (name "Net-(U3-RT)") (class "Default")
      (node (ref "R39") (pin "2") (pinfunction "2_2") (pintype "passive"))
      (node (ref "U3") (pin "4") (pinfunction "RT_4") (pintype "bidirectional"))
    )
    (net (code "62") (name "Net-(U3-SW)") (class "Default")
      (node (ref "C60") (pin "2") (pinfunction "2_2") (pintype "passive"))
      (node (ref "L4") (pin "1") (pinfunction "1_1") (pintype "bidirectional"))
      (node (ref "U3") (pin "2") (pinfunction "SW_2") (pintype "bidirectional"))
    )
    (net (code "63") (name "Net-(U3-TRSS)") (class "Default")
      (node (ref "C43") (pin "1") (pinfunction "1_1") (pintype "passive"))
      (node (ref "U3") (pin "7") (pinfunction "TRSS_7") (pintype "bidirectional"))
    )
    (net (code "64") (name "Net-(U4-BST)") (class "Default")
      (node (ref "C61") (pin "1") (pinfunction "1_1") (pintype "passive"))
      (node (ref "U4") (pin "1") (pinfunction "BST_1") (pintype "bidirectional"))
    )
    (net (code "65") (name "Net-(U4-FB)") (class "Default")
      (node (ref "C49") (pin "1") (pinfunction "1_1") (pintype "passive"))
      (node (ref "R47") (pin "1") (pinfunction "1_1") (pintype "passive"))
      (node (ref "R48") (pin "2") (pinfunction "2_2") (pintype "passive"))
      (node (ref "U4") (pin "6") (pinfunction "FB_6") (pintype "bidirectional"))
    )
    (net (code "66") (name "Net-(U4-INTVCC)") (class "Default")
      (node (ref "C48") (pin "1") (pinfunction "1_1") (pintype "passive"))
      (node (ref "U4") (pin "3") (pinfunction "INTVCC_3") (pintype "bidirectional"))
    )
    (net (code "67") (name "Net-(U4-PG)") (class "Default")
      (node (ref "R46") (pin "1") (pinfunction "1_1") (pintype "passive"))
      (node (ref "U4") (pin "8") (pinfunction "PG_8") (pintype "bidirectional"))
    )
    (net (code "68") (name "Net-(U4-RT)") (class "Default")
      (node (ref "R45") (pin "2") (pinfunction "2_2") (pintype "passive"))
      (node (ref "U4") (pin "4") (pinfunction "RT_4") (pintype "bidirectional"))
    )
    (net (code "69") (name "Net-(U4-SW)") (class "Default")
      (node (ref "C61") (pin "2") (pinfunction "2_2") (pintype "passive"))
      (node (ref "L5") (pin "1") (pinfunction "1_1") (pintype "bidirectional"))
      (node (ref "U4") (pin "2") (pinfunction "SW_2") (pintype "bidirectional"))
    )
    (net (code "70") (name "Net-(U4-TRSS)") (class "Default")
      (node (ref "C47") (pin "1") (pinfunction "1_1") (pintype "passive"))
      (node (ref "U4") (pin "7") (pinfunction "TRSS_7") (pintype "bidirectional"))
    )
    (net (code "71") (name "Net-(U5-BST)") (class "Default")
      (node (ref "C62") (pin "1") (pinfunction "1_1") (pintype "passive"))
      (node (ref "U5") (pin "1") (pinfunction "BST_1") (pintype "bidirectional"))
    )
    (net (code "72") (name "Net-(U5-FB)") (class "Default")
      (node (ref "C54") (pin "1") (pinfunction "1_1") (pintype "passive"))
      (node (ref "R53") (pin "1") (pinfunction "1_1") (pintype "passive"))
      (node (ref "R54") (pin "2") (pinfunction "2_2") (pintype "passive"))
      (node (ref "U5") (pin "6") (pinfunction "FB_6") (pintype "bidirectional"))
    )
    (net (code "73") (name "Net-(U5-INTVCC)") (class "Default")
      (node (ref "C53") (pin "1") (pinfunction "1_1") (pintype "passive"))
      (node (ref "U5") (pin "3") (pinfunction "INTVCC_3") (pintype "bidirectional"))
    )
    (net (code "74") (name "Net-(U5-PG)") (class "Default")
      (node (ref "R52") (pin "1") (pinfunction "1_1") (pintype "passive"))
      (node (ref "U5") (pin "8") (pinfunction "PG_8") (pintype "bidirectional"))
    )
    (net (code "75") (name "Net-(U5-RT)") (class "Default")
      (node (ref "R51") (pin "2") (pinfunction "2_2") (pintype "passive"))
      (node (ref "U5") (pin "4") (pinfunction "RT_4") (pintype "bidirectional"))
    )
    (net (code "76") (name "Net-(U5-SW)") (class "Default")
      (node (ref "C62") (pin "2") (pinfunction "2_2") (pintype "passive"))
      (node (ref "L6") (pin "1") (pinfunction "1_1") (pintype "bidirectional"))
      (node (ref "U5") (pin "2") (pinfunction "SW_2") (pintype "bidirectional"))
    )
    (net (code "77") (name "Net-(U5-TRSS)") (class "Default")
      (node (ref "C52") (pin "1") (pinfunction "1_1") (pintype "passive"))
      (node (ref "U5") (pin "7") (pinfunction "TRSS_7") (pintype "bidirectional"))
    )
    (net (code "78") (name "Net-(U11-CT)") (class "Default")
      (node (ref "R37") (pin "1") (pinfunction "1_1") (pintype "passive"))
      (node (ref "U11") (pin "6") (pinfunction "CT_6") (pintype "bidirectional"))
    )
    (net (code "79") (name "Net-(U11-INT)") (class "Default")
      (node (ref "R38") (pin "1") (pinfunction "1_1") (pintype "passive"))
      (node (ref "U11") (pin "5") (pinfunction "INT_5") (pintype "bidirectional"))
    )
    (net (code "80") (name "Net-(U12-ENABLE)") (class "Default")
      (node (ref "R57") (pin "1") (pinfunction "1_1") (pintype "passive"))
      (node (ref "U12") (pin "8") (pinfunction "ENABLE_8") (pintype "bidirectional"))
    )
    (net (code "81") (name "Net-(U12-RESETIN)") (class "Default")
      (node (ref "R55") (pin "1") (pinfunction "1_1") (pintype "passive"))
      (node (ref "R56") (pin "2") (pinfunction "2_2") (pintype "passive"))
      (node (ref "U12") (pin "2") (pinfunction "RESETIN_2") (pintype "bidirectional"))
    )
    (net (code "82") (name "Net-(U12-SRT)") (class "Default")
      (node (ref "C58") (pin "1") (pinfunction "1_1") (pintype "passive"))
      (node (ref "U12") (pin "3") (pinfunction "SRT_3") (pintype "bidirectional"))
    )
    (net (code "83") (name "Net-(U12-SWT)") (class "Default")
      (node (ref "C59") (pin "1") (pinfunction "1_1") (pintype "passive"))
      (node (ref "U12") (pin "4") (pinfunction "SWT_4") (pintype "bidirectional"))
    )
    (net (code "84") (name "Net-(U13-R1_C1)") (class "Default")
      (node (ref "C63") (pin "2") (pinfunction "2_2") (pintype "passive"))
      (node (ref "R59") (pin "1") (pinfunction "1_1") (pintype "passive"))
      (node (ref "U13") (pin "6") (pinfunction "R1_C1_6") (pintype "input"))
    )
    (net (code "85") (name "Net-(U13-VIN)") (class "Default")
      (node (ref "R59") (pin "2") (pinfunction "2_2") (pintype "passive"))
      (node (ref "R60") (pin "2") (pinfunction "2_2") (pintype "passive"))
      (node (ref "U13") (pin "4") (pinfunction "VIN_4") (pintype "power_in"))
    )
    (net (code "86") (name "PCM_IN") (class "Default")
      (node (ref "C39") (pin "1") (pinfunction "1_1") (pintype "passive"))
      (node (ref "C40") (pin "1") (pinfunction "1_1") (pintype "passive"))
      (node (ref "C41") (pin "1") (pinfunction "1_1") (pintype "passive"))
      (node (ref "FB3") (pin "1") (pinfunction "1_1") (pintype "bidirectional"))
      (node (ref "H1") (pin "2.35") (pinfunction "2.35_2.35") (pintype "bidirectional"))
      (node (ref "H1") (pin "2.36") (pinfunction "2.36_2.36") (pintype "bidirectional"))
    )
    (net (code "87") (name "PCM_IN_FILTERED") (class "Default")
      (node (ref "C33") (pin "1") (pinfunction "1_1") (pintype "passive"))
      (node (ref "C34") (pin "1") (pinfunction "1_1") (pintype "passive"))
      (node (ref "R57") (pin "2") (pinfunction "2_2") (pintype "passive"))
      (node (ref "R60") (pin "1") (pinfunction "1_1") (pintype "passive"))
      (node (ref "R99") (pin "2") (pinfunction "2_2") (pintype "passive"))
      (node (ref "U10") (pin "2") (pinfunction "VIN1_2") (pintype "bidirectional"))
      (node (ref "U10") (pin "3") (pinfunction "VINS_3") (pintype "bidirectional"))
      (node (ref "U10") (pin "7") (pinfunction "VIN2_7") (pintype "bidirectional"))
      (node (ref "U12") (pin "1") (pinfunction "IN_1") (pintype "bidirectional"))
      (node (ref "U3") (pin "9") (pinfunction "VIN_9") (pintype "bidirectional"))
      (node (ref "U4") (pin "9") (pinfunction "VIN_9") (pintype "bidirectional"))
      (node (ref "U5") (pin "9") (pinfunction "VIN_9") (pintype "bidirectional"))
    )
    (net (code "88") (name "RESET_EPS") (class "Default")
      (node (ref "H1") (pin "1.52") (pinfunction "1.52_1.52") (pintype "bidirectional"))
      (node (ref "R58") (pin "1") (pinfunction "1_1") (pintype "passive"))
      (node (ref "TB1") (pin "P28") (pinfunction "RESET_P28") (pintype "bidirectional"))
      (node (ref "TB1") (pin "P3") (pinfunction "RESET_P3") (pintype "bidirectional"))
      (node (ref "U12") (pin "7") (pinfunction "RESET_7") (pintype "bidirectional"))
      (node (ref "U13") (pin "5") (pinfunction "ON_OFF_5") (pintype "input"))
    )
    (net (code "89") (name "SW1") (class "Default")
      (node (ref "C44") (pin "2") (pinfunction "2_2") (pintype "passive"))
      (node (ref "C45") (pin "1") (pinfunction "1_1") (pintype "passive"))
      (node (ref "C46") (pin "1") (pinfunction "1_1") (pintype "passive"))
      (node (ref "H1") (pin "2.8") (pinfunction "2.8_2.8") (pintype "bidirectional"))
      (node (ref "L4") (pin "2") (pinfunction "2_2") (pintype "bidirectional"))
      (node (ref "R41") (pin "2") (pinfunction "2_2") (pintype "passive"))
      (node (ref "R42") (pin "2") (pinfunction "2_2") (pintype "passive"))
    )
    (net (code "90") (name "SW1_EN") (class "Default")
      (node (ref "J10") (pin "6") (pinfunction "1_6") (pintype "passive"))
      (node (ref "TB1") (pin "P7") (pinfunction "D4_P7") (pintype "bidirectional"))
      (node (ref "U3") (pin "10") (pinfunction "EN_10") (pintype "bidirectional"))
    )
    (net (code "91") (name "SW2") (class "Default")
      (node (ref "C65") (pin "1") (pinfunction "1_1") (pintype "passive"))
      (node (ref "H1") (pin "2.13") (pinfunction "2.13_2.13") (pintype "bidirectional"))
      (node (ref "U6") (pin "1") (pinfunction "VOUT_1") (pintype "bidirectional"))
      (node (ref "U6") (pin "8") (pinfunction "VOUT_8") (pintype "bidirectional"))
    )
    (net (code "92") (name "SW2_EN") (class "Default")
      (node (ref "J10") (pin "5") (pinfunction "1_5") (pintype "passive"))
      (node (ref "TB1") (pin "P8") (pinfunction "D5_P8") (pintype "bidirectional"))
      (node (ref "U6") (pin "4") (pinfunction "EN_4") (pintype "bidirectional"))
    )
    (net (code "93") (name "SW3") (class "Default")
      (node (ref "C66") (pin "1") (pinfunction "1_1") (pintype "passive"))
      (node (ref "H1") (pin "2.15") (pinfunction "2.15_2.15") (pintype "bidirectional"))
      (node (ref "U7") (pin "1") (pinfunction "VOUT_1") (pintype "bidirectional"))
      (node (ref "U7") (pin "8") (pinfunction "VOUT_8") (pintype "bidirectional"))
    )
    (net (code "94") (name "SW3_EN") (class "Default")
      (node (ref "J10") (pin "4") (pinfunction "1_4") (pintype "passive"))
      (node (ref "TB1") (pin "P9") (pinfunction "D6_P9") (pintype "bidirectional"))
      (node (ref "U7") (pin "4") (pinfunction "EN_4") (pintype "bidirectional"))
    )
    (net (code "95") (name "SW4") (class "Default")
      (node (ref "C67") (pin "1") (pinfunction "1_1") (pintype "passive"))
      (node (ref "H1") (pin "2.16") (pinfunction "2.16_2.16") (pintype "bidirectional"))
      (node (ref "U8") (pin "1") (pinfunction "VOUT_1") (pintype "bidirectional"))
      (node (ref "U8") (pin "8") (pinfunction "VOUT_8") (pintype "bidirectional"))
    )
    (net (code "96") (name "SW4_EN") (class "Default")
      (node (ref "J10") (pin "3") (pinfunction "1_3") (pintype "passive"))
      (node (ref "TB1") (pin "P10") (pinfunction "D7_P10") (pintype "bidirectional"))
      (node (ref "U8") (pin "4") (pinfunction "EN_4") (pintype "bidirectional"))
    )
    (net (code "97") (name "SW5") (class "Default")
      (node (ref "C68") (pin "1") (pinfunction "1_1") (pintype "passive"))
      (node (ref "H1") (pin "2.19") (pinfunction "2.19_2.19") (pintype "bidirectional"))
      (node (ref "H1") (pin "2.20") (pinfunction "2.20_2.20") (pintype "bidirectional"))
      (node (ref "U9") (pin "1") (pinfunction "VOUT_1") (pintype "bidirectional"))
      (node (ref "U9") (pin "8") (pinfunction "VOUT_8") (pintype "bidirectional"))
    )
    (net (code "98") (name "SW5_EN") (class "Default")
      (node (ref "J10") (pin "2") (pinfunction "1_2") (pintype "passive"))
      (node (ref "TB1") (pin "P12") (pinfunction "D9_P12") (pintype "bidirectional"))
      (node (ref "U9") (pin "4") (pinfunction "EN_4") (pintype "bidirectional"))
    )
    (net (code "99") (name "U2_READY") (class "Default")
      (node (ref "U2") (pin "5") (pinfunction "READY_5") (pintype "bidirectional"))
    )
    (net (code "100") (name "U11_CS") (class "Default")
      (node (ref "TB1") (pin "P11") (pinfunction "D8_P11") (pintype "bidirectional"))
      (node (ref "U11") (pin "4") (pinfunction "CS_4") (pintype "bidirectional"))
    )
    (net (code "101") (name "U11_DIN") (class "Default")
      (node (ref "TB1") (pin "P14") (pinfunction "MOSI_P14") (pintype "bidirectional"))
      (node (ref "U11") (pin "3") (pinfunction "DIN_3") (pintype "bidirectional"))
    )
    (net (code "102") (name "U11_DOUT") (class "Default")
      (node (ref "TB1") (pin "P15") (pinfunction "MISO_P15") (pintype "bidirectional"))
      (node (ref "U11") (pin "2") (pinfunction "DOUT_2") (pintype "bidirectional"))
    )
    (net (code "103") (name "U11_SCLK") (class "Default")
      (node (ref "TB1") (pin "P16") (pinfunction "SCK_P16") (pintype "bidirectional"))
      (node (ref "U11") (pin "1") (pinfunction "SCLK_1") (pintype "bidirectional"))
    )
    (net (code "104") (name "VBAT_BUS") (class "Default")
      (node (ref "C69") (pin "1") (pinfunction "1_1") (pintype "passive"))
      (node (ref "H1") (pin "2.45") (pinfunction "2.45_2.45") (pintype "bidirectional"))
      (node (ref "H1") (pin "2.46") (pinfunction "2.46_2.46") (pintype "bidirectional"))
      (node (ref "U10") (pin "1") (pinfunction "VOUT_1") (pintype "bidirectional"))
      (node (ref "U10") (pin "8") (pinfunction "VOUT_8") (pintype "bidirectional"))
    )
    (net (code "105") (name "VBAT_EN") (class "Default")
      (node (ref "J10") (pin "7") (pinfunction "1_7") (pintype "passive"))
      (node (ref "TB1") (pin "P6") (pinfunction "D3_P6") (pintype "bidirectional"))
      (node (ref "U10") (pin "4") (pinfunction "EN_4") (pintype "bidirectional"))
    )
    (net (code "106") (name "VIN") (class "Default")
      (node (ref "C19") (pin "1") (pinfunction "1_1") (pintype "passive"))
      (node (ref "C20") (pin "1") (pinfunction "1_1") (pintype "passive"))
      (node (ref "C21") (pin "1") (pinfunction "1_1") (pintype "passive"))
      (node (ref "C22") (pin "1") (pinfunction "1_1") (pintype "passive"))
      (node (ref "C31") (pin "1") (pinfunction "1_1") (pintype "passive"))
      (node (ref "D1") (pin "C") (pinfunction "C_C") (pintype "passive"))
      (node (ref "D2") (pin "C") (pinfunction "C_C") (pintype "passive"))
      (node (ref "D3") (pin "C") (pinfunction "C_C") (pintype "passive"))
      (node (ref "D4") (pin "C") (pinfunction "C_C") (pintype "passive"))
      (node (ref "D5") (pin "C") (pinfunction "C_C") (pintype "passive"))
      (node (ref "D6") (pin "C") (pinfunction "C_C") (pintype "passive"))
      (node (ref "D7") (pin "C") (pinfunction "C_C") (pintype "passive"))
      (node (ref "L2") (pin "1") (pinfunction "1_1") (pintype "bidirectional"))
    )
    (net (code "107") (name "VIN_LT8390") (class "Default")
      (node (ref "C1") (pin "1") (pinfunction "1_1") (pintype "passive"))
      (node (ref "C10") (pin "1") (pinfunction "1_1") (pintype "passive"))
      (node (ref "C11") (pin "1") (pinfunction "1_1") (pintype "passive"))
      (node (ref "C12") (pin "1") (pinfunction "1_1") (pintype "passive"))
      (node (ref "C17") (pin "1") (pinfunction "1_1") (pintype "passive"))
      (node (ref "C18") (pin "1") (pinfunction "1_1") (pintype "passive"))
      (node (ref "C35") (pin "1") (pinfunction "1_1") (pintype "passive"))
      (node (ref "C9") (pin "1") (pinfunction "1_1") (pintype "passive"))
      (node (ref "L2") (pin "2") (pinfunction "2_2") (pintype "bidirectional"))
      (node (ref "M1") (pin "8") (pinfunction "D_8") (pintype "passive"))
      (node (ref "M5") (pin "8") (pinfunction "D_8") (pintype "passive"))
      (node (ref "R25") (pin "2") (pinfunction "2_2") (pintype "passive"))
      (node (ref "R26") (pin "2") (pinfunction "2_2") (pintype "passive"))
      (node (ref "R27") (pin "1") (pinfunction "1_1") (pintype "passive"))
      (node (ref "R27") (pin "2") (pinfunction "2_2") (pintype "passive"))
      (node (ref "R29") (pin "2") (pinfunction "2_2") (pintype "passive"))
      (node (ref "R9") (pin "2") (pinfunction "2_2") (pintype "passive"))
      (node (ref "U1") (pin "7") (pinfunction "VIN_7") (pintype "bidirectional"))
    )
    (net (code "108") (name "VREF_LT8390") (class "Default")
      (node (ref "C3") (pin "2") (pinfunction "2_2") (pintype "passive"))
      (node (ref "R19") (pin "2") (pinfunction "2_2") (pintype "passive"))
      (node (ref "R20") (pin "1") (pinfunction "1_1") (pintype "passive"))
      (node (ref "R22") (pin "1") (pinfunction "1_1") (pintype "passive"))
      (node (ref "U1") (pin "12") (pinfunction "VREF_12") (pintype "bidirectional"))
    )
    (net (code "109") (name "unconnected-(H1-Pad1.1)") (class "Default")
      (node (ref "H1") (pin "1.1") (pinfunction "1.1_1.1") (pintype "bidirectional"))
    )
    (net (code "110") (name "unconnected-(H1-Pad1.2)") (class "Default")
      (node (ref "H1") (pin "1.2") (pinfunction "1.2_1.2") (pintype "bidirectional"))
    )
    (net (code "111") (name "unconnected-(H1-Pad1.3)") (class "Default")
      (node (ref "H1") (pin "1.3") (pinfunction "1.3_1.3") (pintype "bidirectional"))
    )
    (net (code "112") (name "unconnected-(H1-Pad1.4)") (class "Default")
      (node (ref "H1") (pin "1.4") (pinfunction "1.4_1.4") (pintype "bidirectional"))
    )
    (net (code "113") (name "unconnected-(H1-Pad1.5)") (class "Default")
      (node (ref "H1") (pin "1.5") (pinfunction "1.5_1.5") (pintype "bidirectional"))
    )
    (net (code "114") (name "unconnected-(H1-Pad1.6)") (class "Default")
      (node (ref "H1") (pin "1.6") (pinfunction "1.6_1.6") (pintype "bidirectional"))
    )
    (net (code "115") (name "unconnected-(H1-Pad1.7)") (class "Default")
      (node (ref "H1") (pin "1.7") (pinfunction "1.7_1.7") (pintype "bidirectional"))
    )
    (net (code "116") (name "unconnected-(H1-Pad1.8)") (class "Default")
      (node (ref "H1") (pin "1.8") (pinfunction "1.8_1.8") (pintype "bidirectional"))
    )
    (net (code "117") (name "unconnected-(H1-Pad1.9)") (class "Default")
      (node (ref "H1") (pin "1.9") (pinfunction "1.9_1.9") (pintype "bidirectional"))
    )
    (net (code "118") (name "unconnected-(H1-Pad1.10)") (class "Default")
      (node (ref "H1") (pin "1.10") (pinfunction "1.10_1.10") (pintype "bidirectional"))
    )
    (net (code "119") (name "unconnected-(H1-Pad1.11)") (class "Default")
      (node (ref "H1") (pin "1.11") (pinfunction "1.11_1.11") (pintype "bidirectional"))
    )
    (net (code "120") (name "unconnected-(H1-Pad1.12)") (class "Default")
      (node (ref "H1") (pin "1.12") (pinfunction "1.12_1.12") (pintype "bidirectional"))
    )
    (net (code "121") (name "unconnected-(H1-Pad1.13)") (class "Default")
      (node (ref "H1") (pin "1.13") (pinfunction "1.13_1.13") (pintype "bidirectional"))
    )
    (net (code "122") (name "unconnected-(H1-Pad1.14)") (class "Default")
      (node (ref "H1") (pin "1.14") (pinfunction "1.14_1.14") (pintype "bidirectional"))
    )
    (net (code "123") (name "unconnected-(H1-Pad1.15)") (class "Default")
      (node (ref "H1") (pin "1.15") (pinfunction "1.15_1.15") (pintype "bidirectional"))
    )
    (net (code "124") (name "unconnected-(H1-Pad1.16)") (class "Default")
      (node (ref "H1") (pin "1.16") (pinfunction "1.16_1.16") (pintype "bidirectional"))
    )
    (net (code "125") (name "unconnected-(H1-Pad1.17)") (class "Default")
      (node (ref "H1") (pin "1.17") (pinfunction "1.17_1.17") (pintype "bidirectional"))
    )
    (net (code "126") (name "unconnected-(H1-Pad1.18)") (class "Default")
      (node (ref "H1") (pin "1.18") (pinfunction "1.18_1.18") (pintype "bidirectional"))
    )
    (net (code "127") (name "unconnected-(H1-Pad1.19)") (class "Default")
      (node (ref "H1") (pin "1.19") (pinfunction "1.19_1.19") (pintype "bidirectional"))
    )
    (net (code "128") (name "unconnected-(H1-Pad1.20)") (class "Default")
      (node (ref "H1") (pin "1.20") (pinfunction "1.20_1.20") (pintype "bidirectional"))
    )
    (net (code "129") (name "unconnected-(H1-Pad1.21)") (class "Default")
      (node (ref "H1") (pin "1.21") (pinfunction "1.21_1.21") (pintype "bidirectional"))
    )
    (net (code "130") (name "unconnected-(H1-Pad1.22)") (class "Default")
      (node (ref "H1") (pin "1.22") (pinfunction "1.22_1.22") (pintype "bidirectional"))
    )
    (net (code "131") (name "unconnected-(H1-Pad1.23)") (class "Default")
      (node (ref "H1") (pin "1.23") (pinfunction "1.23_1.23") (pintype "bidirectional"))
    )
    (net (code "132") (name "unconnected-(H1-Pad1.24)") (class "Default")
      (node (ref "H1") (pin "1.24") (pinfunction "1.24_1.24") (pintype "bidirectional"))
    )
    (net (code "133") (name "unconnected-(H1-Pad1.25)") (class "Default")
      (node (ref "H1") (pin "1.25") (pinfunction "1.25_1.25") (pintype "bidirectional"))
    )
    (net (code "134") (name "unconnected-(H1-Pad1.26)") (class "Default")
      (node (ref "H1") (pin "1.26") (pinfunction "1.26_1.26") (pintype "bidirectional"))
    )
    (net (code "135") (name "unconnected-(H1-Pad1.27)") (class "Default")
      (node (ref "H1") (pin "1.27") (pinfunction "1.27_1.27") (pintype "bidirectional"))
    )
    (net (code "136") (name "unconnected-(H1-Pad1.28)") (class "Default")
      (node (ref "H1") (pin "1.28") (pinfunction "1.28_1.28") (pintype "bidirectional"))
    )
    (net (code "137") (name "unconnected-(H1-Pad1.29)") (class "Default")
      (node (ref "H1") (pin "1.29") (pinfunction "1.29_1.29") (pintype "bidirectional"))
    )
    (net (code "138") (name "unconnected-(H1-Pad1.30)") (class "Default")
      (node (ref "H1") (pin "1.30") (pinfunction "1.30_1.30") (pintype "bidirectional"))
    )
    (net (code "139") (name "unconnected-(H1-Pad1.31)") (class "Default")
      (node (ref "H1") (pin "1.31") (pinfunction "1.31_1.31") (pintype "bidirectional"))
    )
    (net (code "140") (name "unconnected-(H1-Pad1.33)") (class "Default")
      (node (ref "H1") (pin "1.33") (pinfunction "1.33_1.33") (pintype "bidirectional"))
    )
    (net (code "141") (name "unconnected-(H1-Pad1.34)") (class "Default")
      (node (ref "H1") (pin "1.34") (pinfunction "1.34_1.34") (pintype "bidirectional"))
    )
    (net (code "142") (name "unconnected-(H1-Pad1.35)") (class "Default")
      (node (ref "H1") (pin "1.35") (pinfunction "1.35_1.35") (pintype "bidirectional"))
    )
    (net (code "143") (name "unconnected-(H1-Pad1.36)") (class "Default")
      (node (ref "H1") (pin "1.36") (pinfunction "1.36_1.36") (pintype "bidirectional"))
    )
    (net (code "144") (name "unconnected-(H1-Pad1.37)") (class "Default")
      (node (ref "H1") (pin "1.37") (pinfunction "1.37_1.37") (pintype "bidirectional"))
    )
    (net (code "145") (name "unconnected-(H1-Pad1.38)") (class "Default")
      (node (ref "H1") (pin "1.38") (pinfunction "1.38_1.38") (pintype "bidirectional"))
    )
    (net (code "146") (name "unconnected-(H1-Pad1.39)") (class "Default")
      (node (ref "H1") (pin "1.39") (pinfunction "1.39_1.39") (pintype "bidirectional"))
    )
    (net (code "147") (name "unconnected-(H1-Pad1.40)") (class "Default")
      (node (ref "H1") (pin "1.40") (pinfunction "1.40_1.40") (pintype "bidirectional"))
    )
    (net (code "148") (name "unconnected-(H1-Pad1.42)") (class "Default")
      (node (ref "H1") (pin "1.42") (pinfunction "1.42_1.42") (pintype "bidirectional"))
    )
    (net (code "149") (name "unconnected-(H1-Pad1.44)") (class "Default")
      (node (ref "H1") (pin "1.44") (pinfunction "1.44_1.44") (pintype "bidirectional"))
    )
    (net (code "150") (name "unconnected-(H1-Pad1.45)") (class "Default")
      (node (ref "H1") (pin "1.45") (pinfunction "1.45_1.45") (pintype "bidirectional"))
    )
    (net (code "151") (name "unconnected-(H1-Pad1.46)") (class "Default")
      (node (ref "H1") (pin "1.46") (pinfunction "1.46_1.46") (pintype "bidirectional"))
    )
    (net (code "152") (name "unconnected-(H1-Pad1.47)") (class "Default")
      (node (ref "H1") (pin "1.47") (pinfunction "1.47_1.47") (pintype "bidirectional"))
    )
    (net (code "153") (name "unconnected-(H1-Pad1.48)") (class "Default")
      (node (ref "H1") (pin "1.48") (pinfunction "1.48_1.48") (pintype "bidirectional"))
    )
    (net (code "154") (name "unconnected-(H1-Pad1.50)") (class "Default")
      (node (ref "H1") (pin "1.50") (pinfunction "1.50_1.50") (pintype "bidirectional"))
    )
    (net (code "155") (name "unconnected-(H1-Pad2.1)") (class "Default")
      (node (ref "H1") (pin "2.1") (pinfunction "2.1_2.1") (pintype "bidirectional"))
    )
    (net (code "156") (name "unconnected-(H1-Pad2.2)") (class "Default")
      (node (ref "H1") (pin "2.2") (pinfunction "2.2_2.2") (pintype "bidirectional"))
    )
    (net (code "157") (name "unconnected-(H1-Pad2.3)") (class "Default")
      (node (ref "H1") (pin "2.3") (pinfunction "2.3_2.3") (pintype "bidirectional"))
    )
    (net (code "158") (name "unconnected-(H1-Pad2.4)") (class "Default")
      (node (ref "H1") (pin "2.4") (pinfunction "2.4_2.4") (pintype "bidirectional"))
    )
    (net (code "159") (name "unconnected-(H1-Pad2.5)") (class "Default")
      (node (ref "H1") (pin "2.5") (pinfunction "2.5_2.5") (pintype "bidirectional"))
    )
    (net (code "160") (name "unconnected-(H1-Pad2.6)") (class "Default")
      (node (ref "H1") (pin "2.6") (pinfunction "2.6_2.6") (pintype "bidirectional"))
    )
    (net (code "161") (name "unconnected-(H1-Pad2.7)") (class "Default")
      (node (ref "H1") (pin "2.7") (pinfunction "2.7_2.7") (pintype "bidirectional"))
    )
    (net (code "162") (name "unconnected-(H1-Pad2.10)") (class "Default")
      (node (ref "H1") (pin "2.10") (pinfunction "2.10_2.10") (pintype "bidirectional"))
    )
    (net (code "163") (name "unconnected-(H1-Pad2.11)") (class "Default")
      (node (ref "H1") (pin "2.11") (pinfunction "2.11_2.11") (pintype "bidirectional"))
    )
    (net (code "164") (name "unconnected-(H1-Pad2.12)") (class "Default")
      (node (ref "H1") (pin "2.12") (pinfunction "2.12_2.12") (pintype "bidirectional"))
    )
    (net (code "165") (name "unconnected-(H1-Pad2.18)") (class "Default")
      (node (ref "H1") (pin "2.18") (pinfunction "2.18_2.18") (pintype "bidirectional"))
    )
    (net (code "166") (name "unconnected-(H1-Pad2.23)") (class "Default")
      (node (ref "H1") (pin "2.23") (pinfunction "2.23_2.23") (pintype "bidirectional"))
    )
    (net (code "167") (name "unconnected-(H1-Pad2.24)") (class "Default")
      (node (ref "H1") (pin "2.24") (pinfunction "2.24_2.24") (pintype "bidirectional"))
    )
    (net (code "168") (name "unconnected-(H1-Pad2.31)") (class "Default")
      (node (ref "H1") (pin "2.31") (pinfunction "2.31_2.31") (pintype "bidirectional"))
    )
    (net (code "169") (name "unconnected-(H1-Pad2.33)") (class "Default")
      (node (ref "H1") (pin "2.33") (pinfunction "2.33_2.33") (pintype "bidirectional"))
    )
    (net (code "170") (name "unconnected-(H1-Pad2.34)") (class "Default")
      (node (ref "H1") (pin "2.34") (pinfunction "2.34_2.34") (pintype "bidirectional"))
    )
    (net (code "171") (name "unconnected-(H1-Pad2.37)") (class "Default")
      (node (ref "H1") (pin "2.37") (pinfunction "2.37_2.37") (pintype "bidirectional"))
    )
    (net (code "172") (name "unconnected-(H1-Pad2.38)") (class "Default")
      (node (ref "H1") (pin "2.38") (pinfunction "2.38_2.38") (pintype "bidirectional"))
    )
    (net (code "173") (name "unconnected-(H1-Pad2.39)") (class "Default")
      (node (ref "H1") (pin "2.39") (pinfunction "2.39_2.39") (pintype "bidirectional"))
    )
    (net (code "174") (name "unconnected-(H1-Pad2.40)") (class "Default")
      (node (ref "H1") (pin "2.40") (pinfunction "2.40_2.40") (pintype "bidirectional"))
    )
    (net (code "175") (name "unconnected-(H1-Pad2.49)") (class "Default")
      (node (ref "H1") (pin "2.49") (pinfunction "2.49_2.49") (pintype "bidirectional"))
    )
    (net (code "176") (name "unconnected-(H1-Pad2.50)") (class "Default")
      (node (ref "H1") (pin "2.50") (pinfunction "2.50_2.50") (pintype "bidirectional"))
    )
    (net (code "177") (name "unconnected-(H1-Pad2.51)") (class "Default")
      (node (ref "H1") (pin "2.51") (pinfunction "2.51_2.51") (pintype "bidirectional"))
    )
    (net (code "178") (name "unconnected-(H1-Pad2.52)") (class "Default")
      (node (ref "H1") (pin "2.52") (pinfunction "2.52_2.52") (pintype "bidirectional"))
    )
    (net (code "179") (name "unconnected-(TB1-+5V-PadP27)") (class "Default")
      (node (ref "TB1") (pin "P27") (pinfunction "+5V_P27") (pintype "bidirectional"))
    )
    (net (code "180") (name "unconnected-(TB1-AIN0-PadP22)") (class "Default")
      (node (ref "TB1") (pin "P22") (pinfunction "AIN0_P22") (pintype "bidirectional"))
    )
    (net (code "181") (name "unconnected-(TB1-AIN1-PadP21)") (class "Default")
      (node (ref "TB1") (pin "P21") (pinfunction "AIN1_P21") (pintype "bidirectional"))
    )
    (net (code "182") (name "unconnected-(TB1-AIN2-PadP20)") (class "Default")
      (node (ref "TB1") (pin "P20") (pinfunction "AIN2_P20") (pintype "bidirectional"))
    )
    (net (code "183") (name "unconnected-(TB1-AIN3-PadP19)") (class "Default")
      (node (ref "TB1") (pin "P19") (pinfunction "AIN3_P19") (pintype "bidirectional"))
    )
    (net (code "184") (name "unconnected-(TB1-AIN4-PadP25)") (class "Default")
      (node (ref "TB1") (pin "P25") (pinfunction "AIN4_P25") (pintype "bidirectional"))
    )
    (net (code "185") (name "unconnected-(TB1-AIN5-PadP26)") (class "Default")
      (node (ref "TB1") (pin "P26") (pinfunction "AIN5_P26") (pintype "bidirectional"))
    )
    (net (code "186") (name "unconnected-(TB1-AREF-PadP18)") (class "Default")
      (node (ref "TB1") (pin "P18") (pinfunction "AREF_P18") (pintype "bidirectional"))
    )
    (net (code "187") (name "unconnected-(U1-ISMON-Pad16)") (class "Default")
      (node (ref "U1") (pin "16") (pinfunction "ISMON_16") (pintype "bidirectional"))
    )
    (net (code "188") (name "unconnected-(U1-LOADTG-Pad23)") (class "Default")
      (node (ref "U1") (pin "23") (pinfunction "LOADTG_23") (pintype "bidirectional"))
    )
    (net (code "189") (name "unconnected-(U6-VIN3-Pad6)") (class "Default")
      (node (ref "U6") (pin "6") (pinfunction "VIN3_6") (pintype "bidirectional"))
    )
    (net (code "190") (name "unconnected-(U7-VIN3-Pad6)") (class "Default")
      (node (ref "U7") (pin "6") (pinfunction "VIN3_6") (pintype "bidirectional"))
    )
    (net (code "191") (name "unconnected-(U8-VIN3-Pad6)") (class "Default")
      (node (ref "U8") (pin "6") (pinfunction "VIN3_6") (pintype "bidirectional"))
    )
    (net (code "192") (name "unconnected-(U9-VIN3-Pad6)") (class "Default")
      (node (ref "U9") (pin "6") (pinfunction "VIN3_6") (pintype "bidirectional"))
    )
    (net (code "193") (name "unconnected-(U10-VIN3-Pad6)") (class "Default")
      (node (ref "U10") (pin "6") (pinfunction "VIN3_6") (pintype "bidirectional"))
    )
  )
)
